# controller.net
KiCad netlist of a schematic drawn in EAGLE
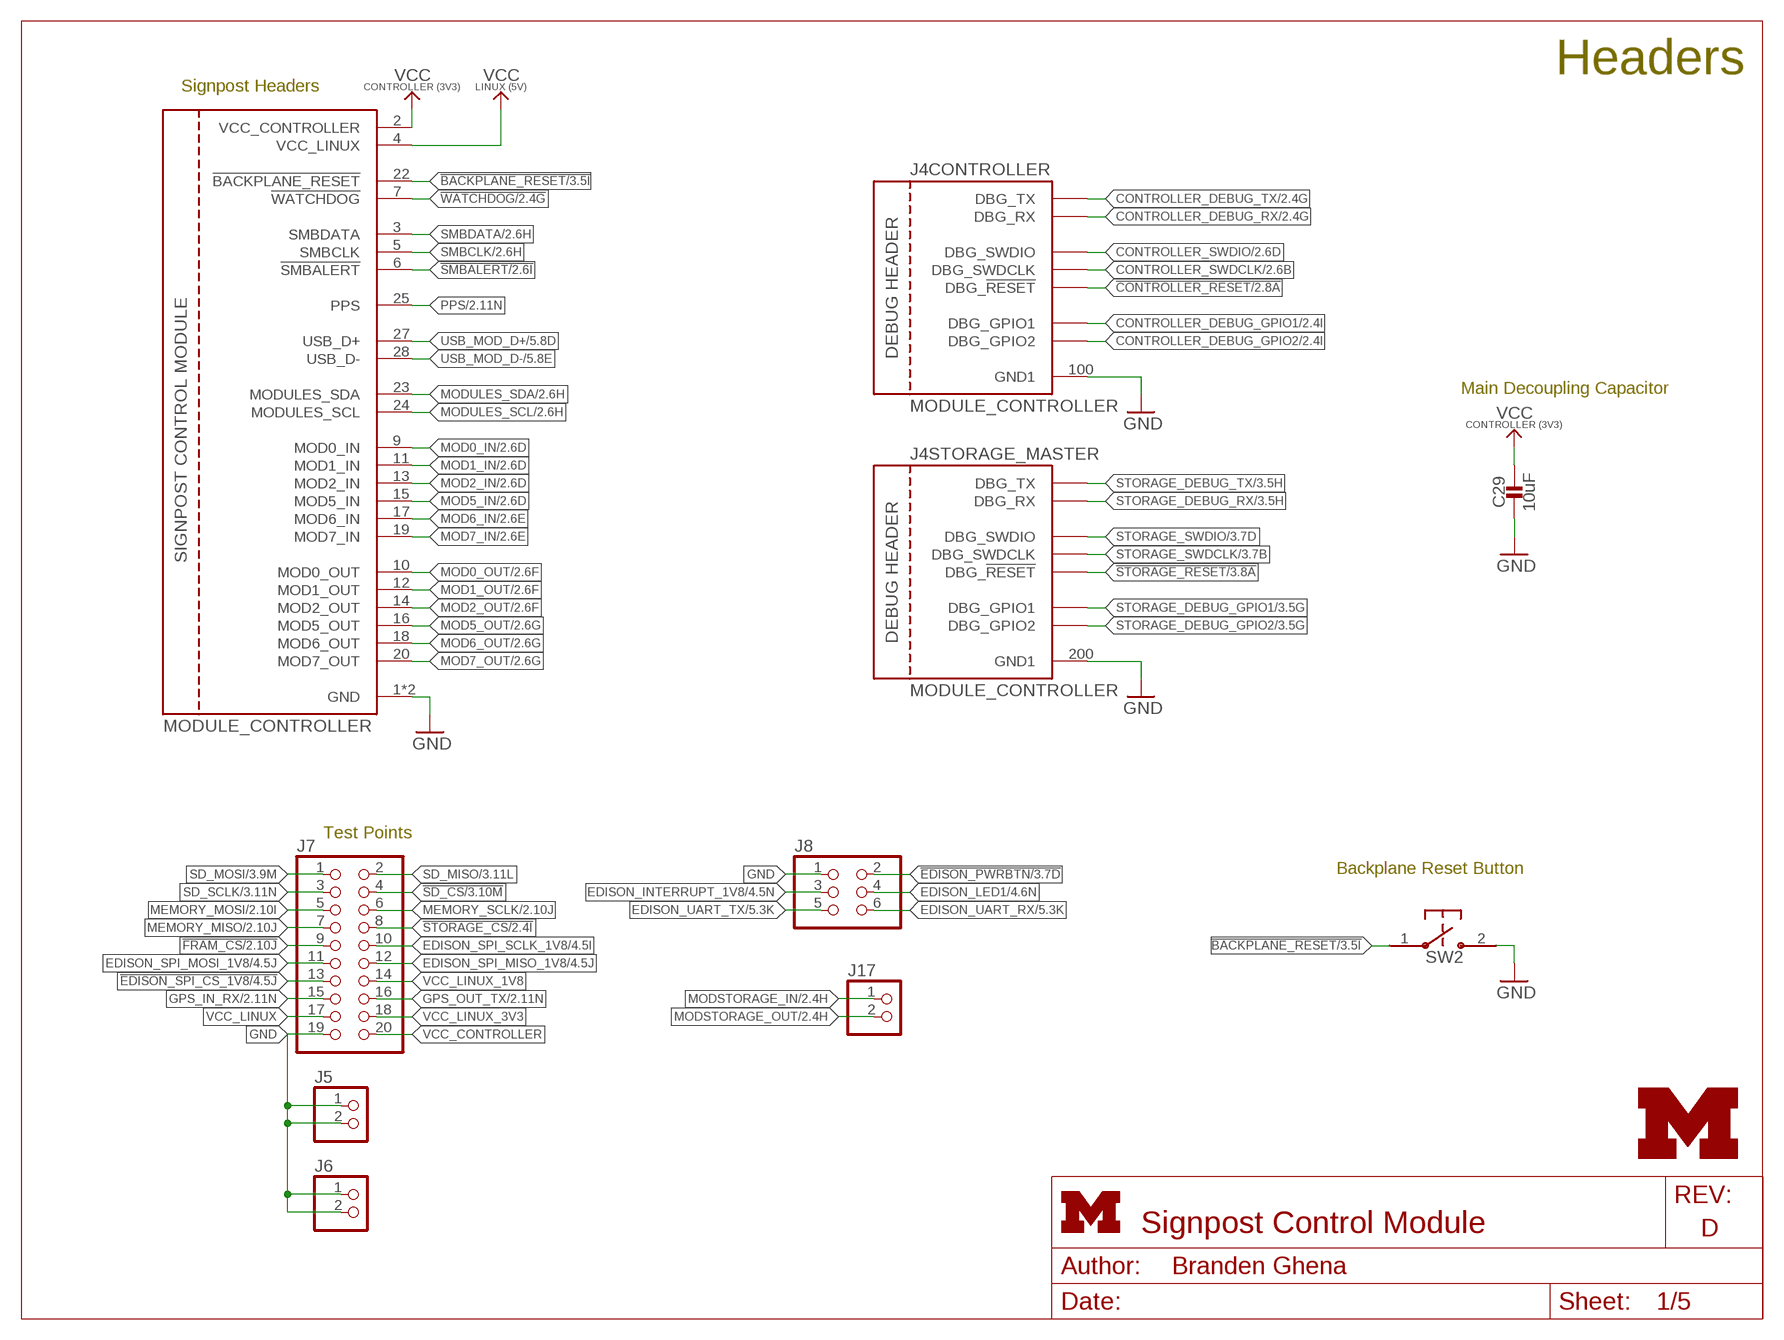
[diagram p0: schematic, sheet 1]
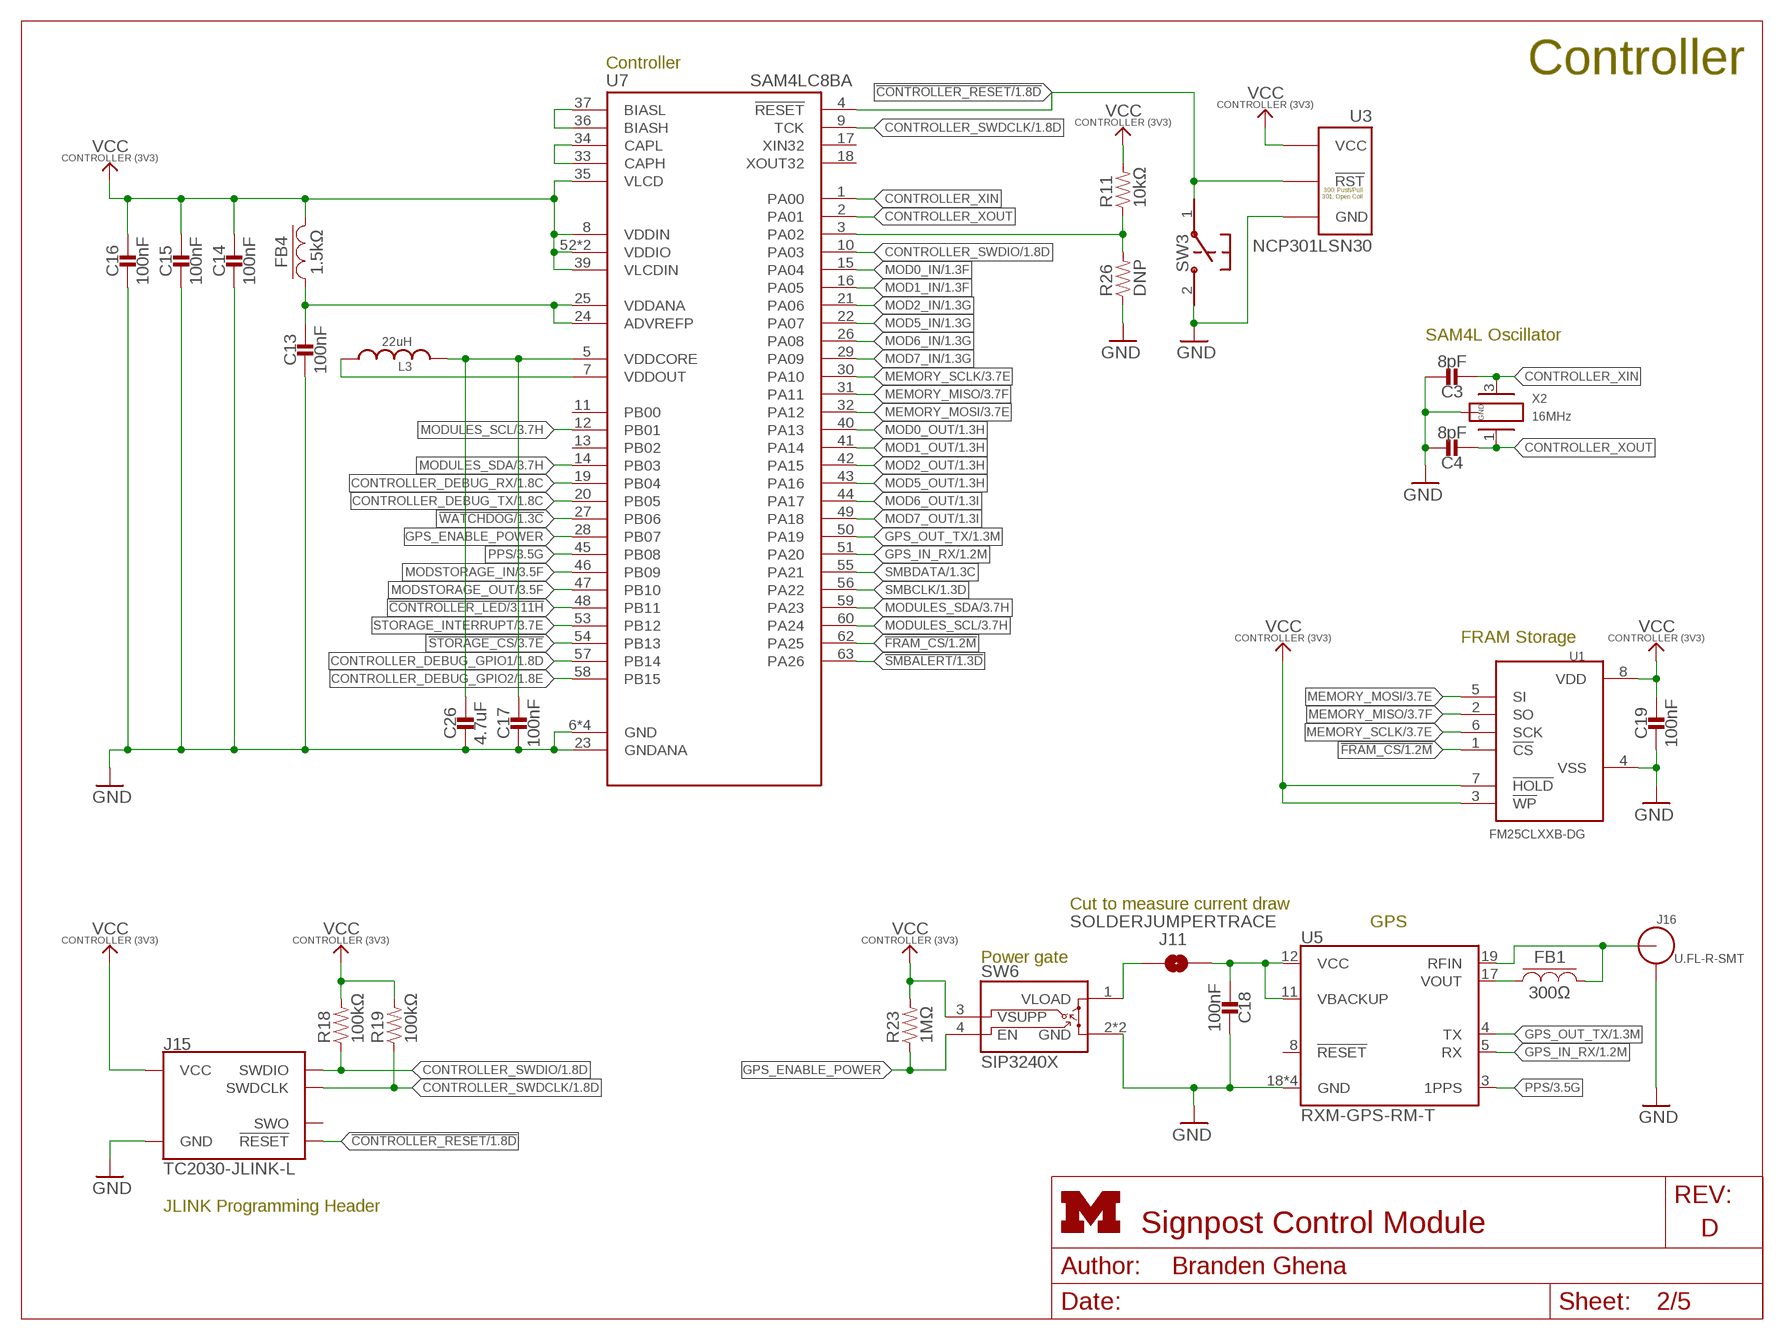
[diagram p1: schematic, sheet 2]
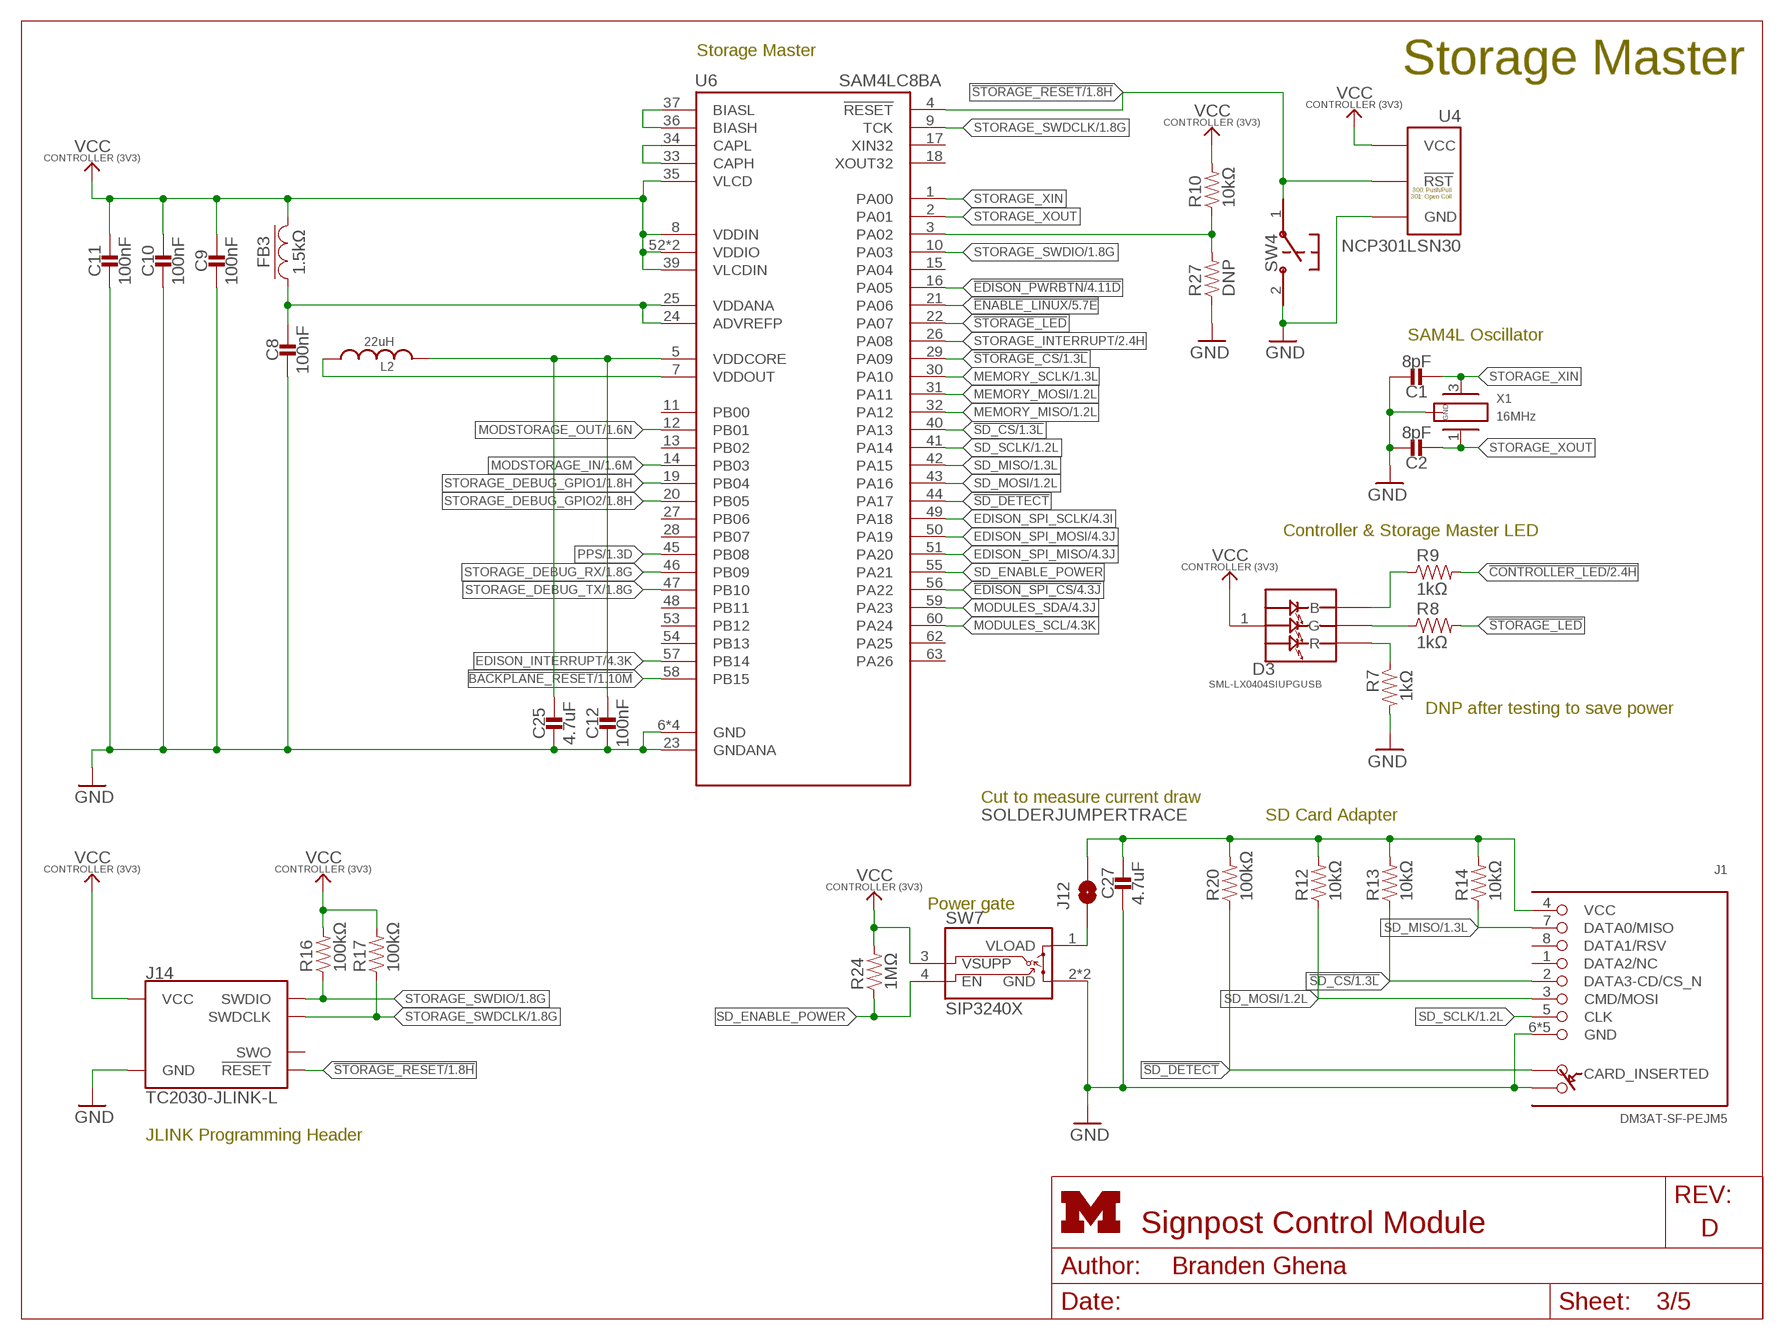
[diagram p2: schematic, sheet 3]
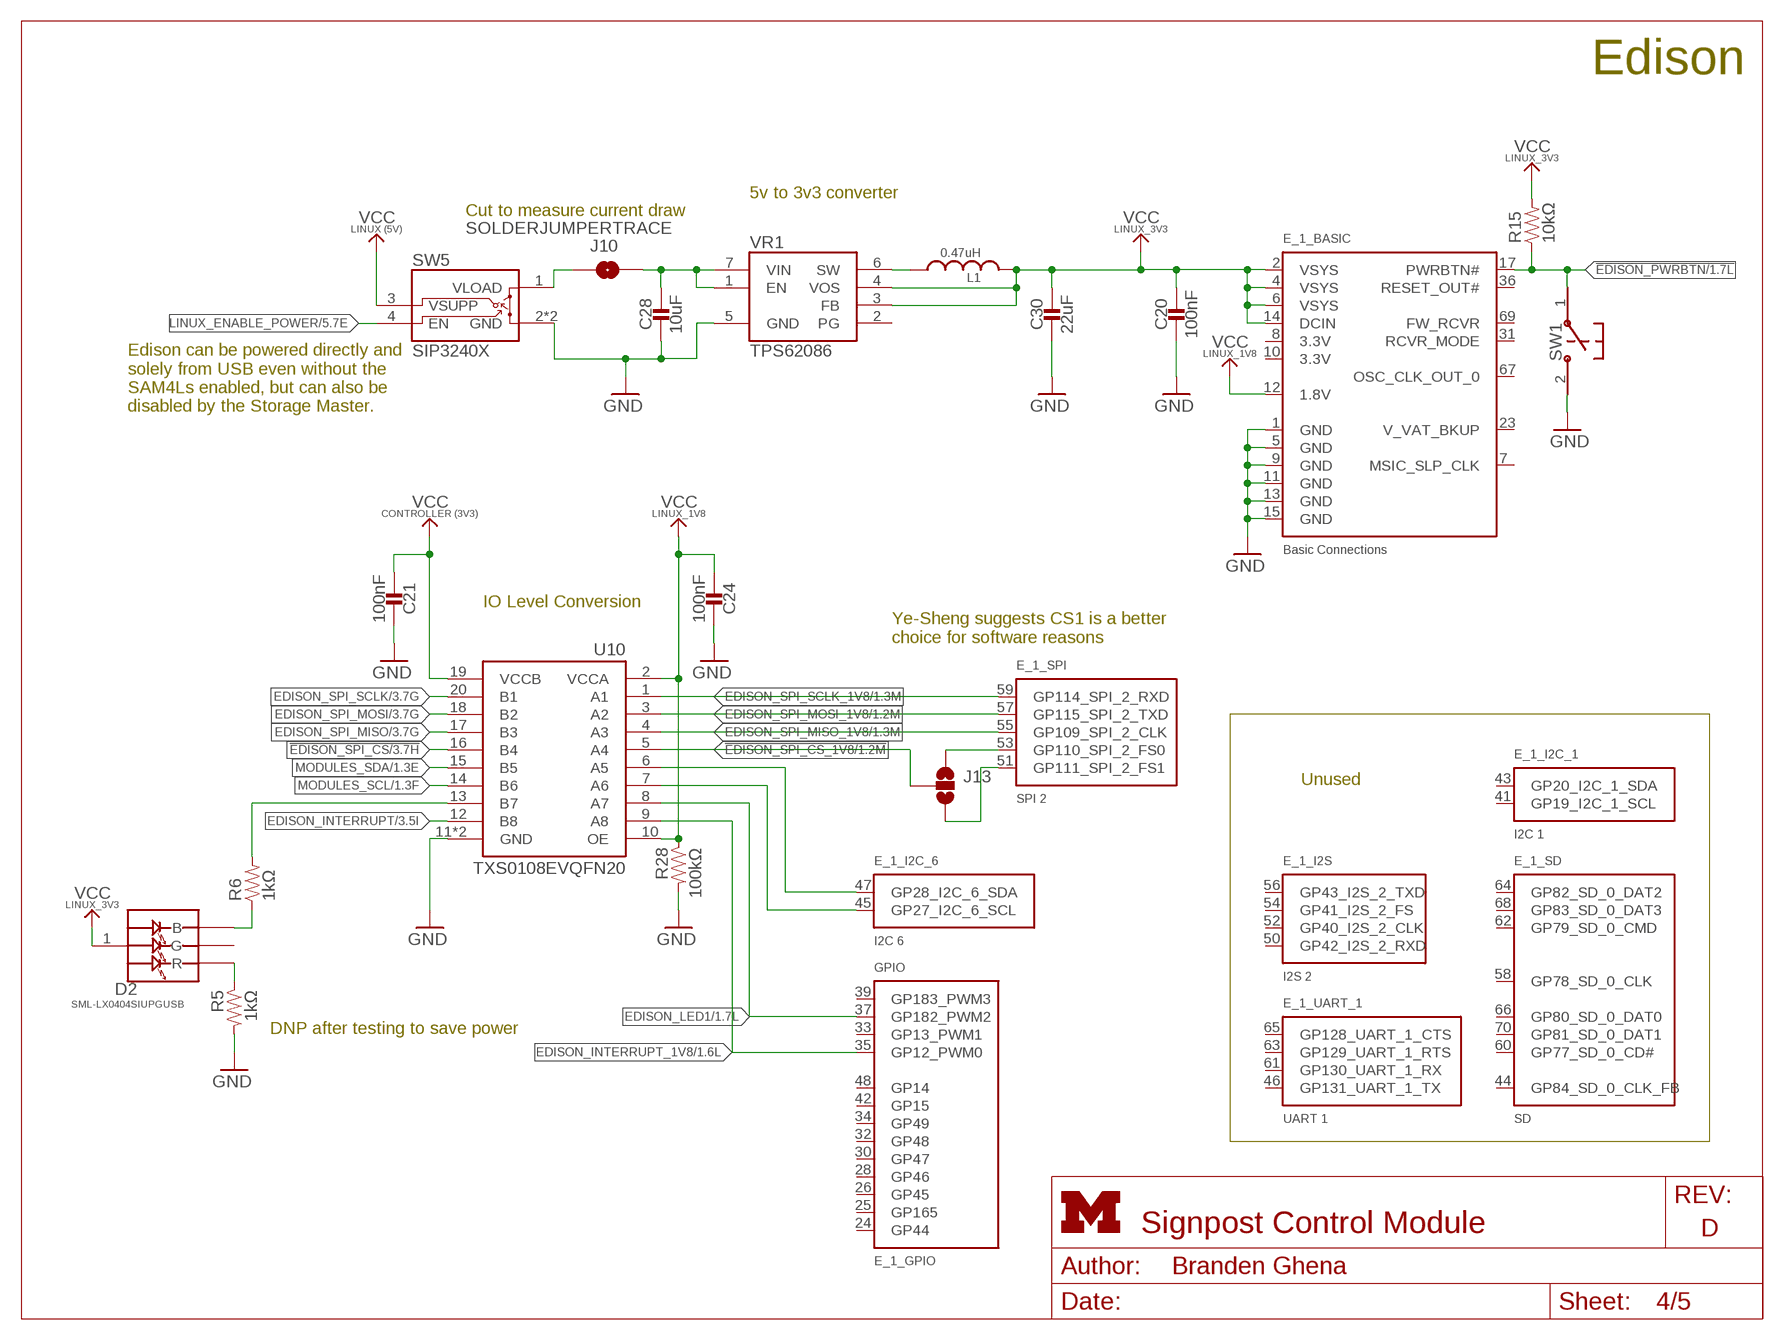
[diagram p3: schematic, sheet 4]
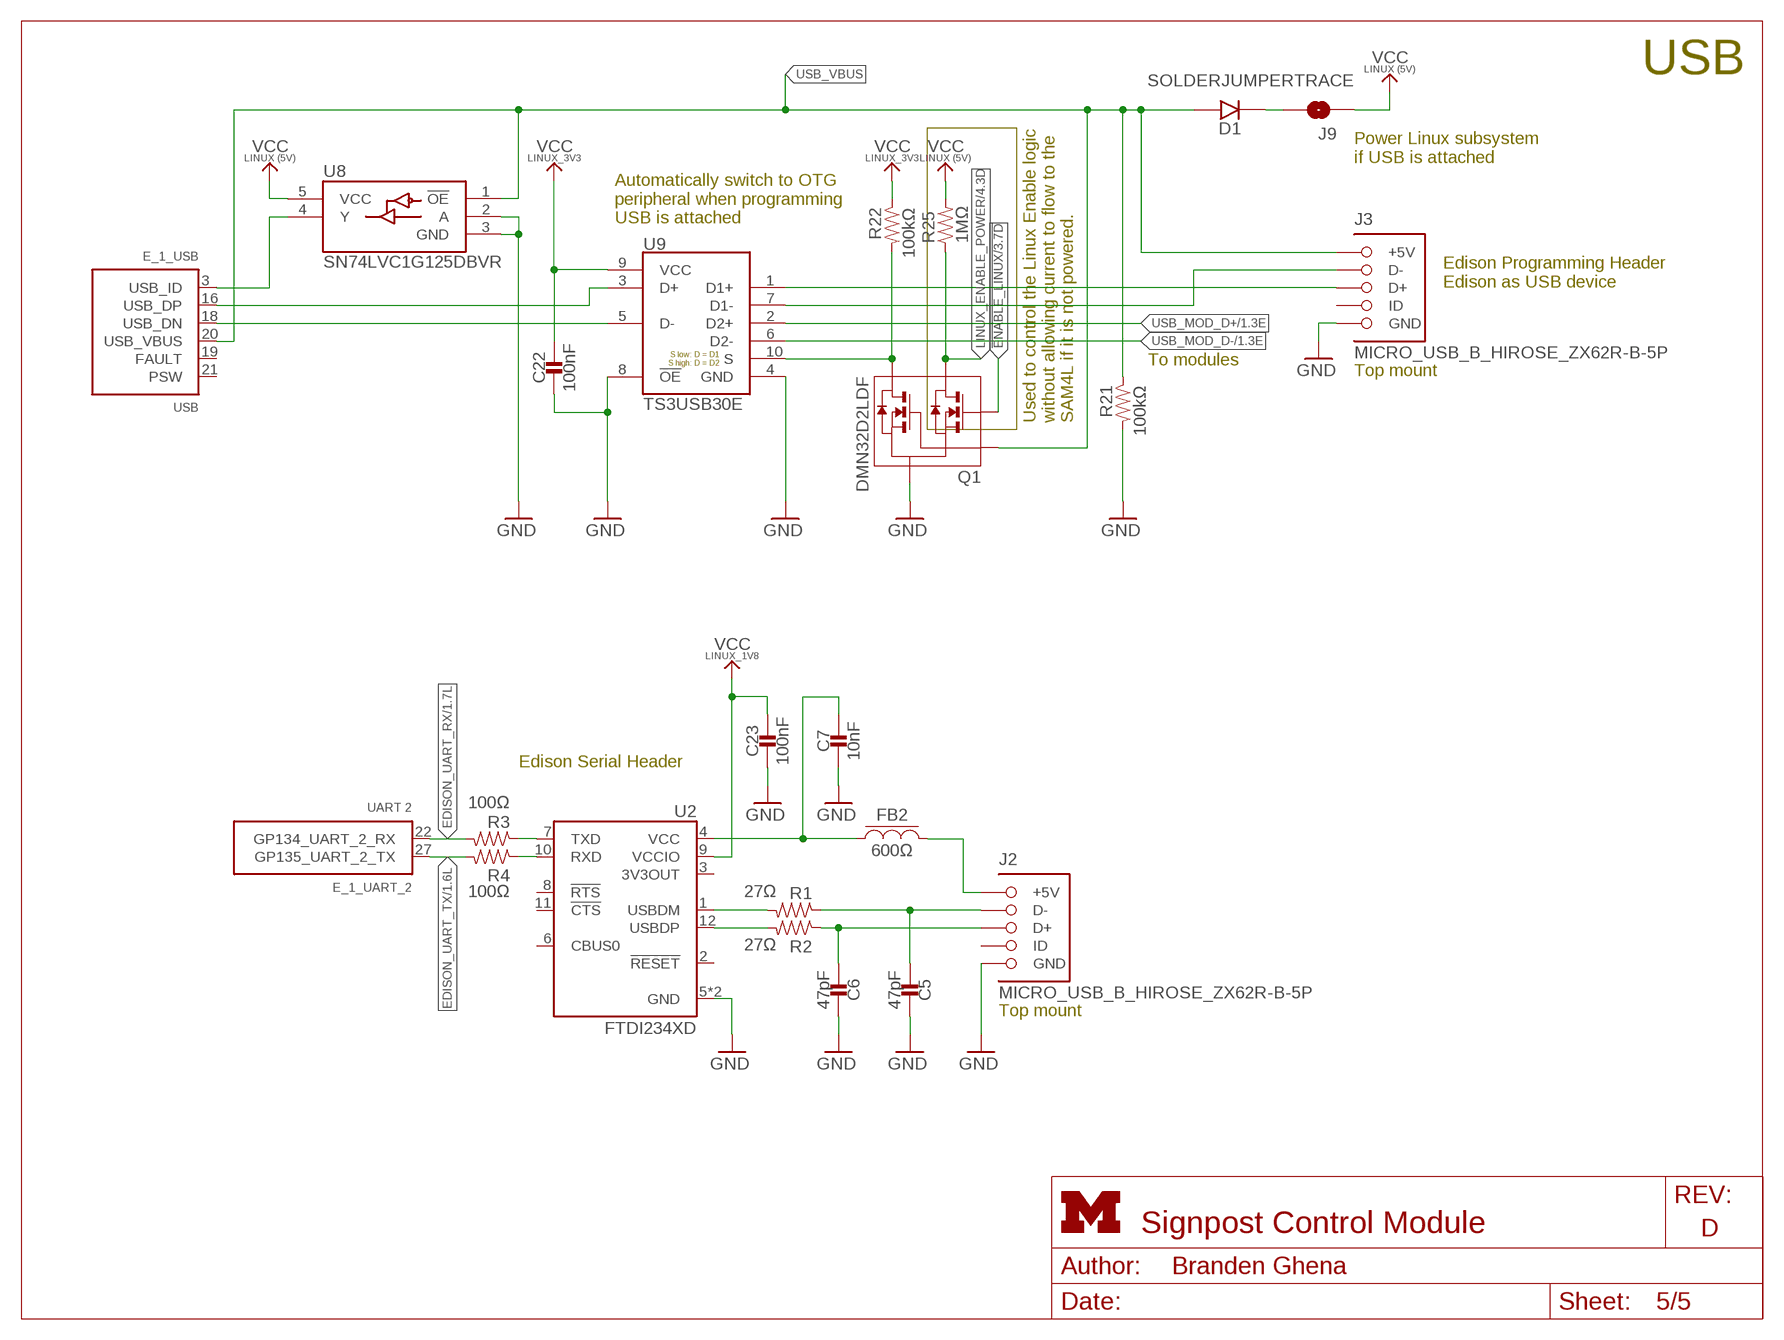
[diagram p4: schematic, sheet 5]

(export (version "E")
  (design (tool "Eeschema 10.0.6"))
  (components
    (comp (ref "C3")
      (value "8pF")
      (footprint "eagle-import:0402_CAP")
      (libsource (lib "eagle-import") (part "CAPACITOR0402_CAP"))
    )
    (comp (ref "C4")
      (value "8pF")
      (footprint "eagle-import:0402_CAP")
      (libsource (lib "eagle-import") (part "CAPACITOR0402_CAP"))
    )
    (comp (ref "C13")
      (value "100nF")
      (footprint "eagle-import:0402_CAP")
      (libsource (lib "eagle-import") (part "CAPACITOR0402_CAP"))
    )
    (comp (ref "C14")
      (value "100nF")
      (footprint "eagle-import:0402_CAP")
      (libsource (lib "eagle-import") (part "CAPACITOR0402_CAP"))
    )
    (comp (ref "C15")
      (value "100nF")
      (footprint "eagle-import:0402_CAP")
      (libsource (lib "eagle-import") (part "CAPACITOR0402_CAP"))
    )
    (comp (ref "C16")
      (value "100nF")
      (footprint "eagle-import:0402_CAP")
      (libsource (lib "eagle-import") (part "CAPACITOR0402_CAP"))
    )
    (comp (ref "C17")
      (value "100nF")
      (footprint "eagle-import:0402_CAP")
      (libsource (lib "eagle-import") (part "CAPACITOR0402_CAP"))
    )
    (comp (ref "C18")
      (value "100nF")
      (footprint "eagle-import:0402_CAP")
      (libsource (lib "eagle-import") (part "CAPACITOR0402_CAP"))
    )
    (comp (ref "C19")
      (value "100nF")
      (footprint "eagle-import:0402_CAP")
      (libsource (lib "eagle-import") (part "CAPACITOR0402_CAP"))
    )
    (comp (ref "C26")
      (value "4.7uF")
      (footprint "eagle-import:0402_CAP")
      (libsource (lib "eagle-import") (part "CAPACITOR0402_CAP"))
    )
    (comp (ref "FB1")
      (value "300Ω")
      (footprint "eagle-import:0402_CAP")
      (libsource (lib "eagle-import") (part "FERRITE_BEAD0402"))
    )
    (comp (ref "FB4")
      (value "1.5kΩ")
      (footprint "eagle-import:0402_CAP")
      (libsource (lib "eagle-import") (part "FERRITE_BEAD0402"))
    )
    (comp (ref "J11")
      (value "SOLDERJUMPERTRACE")
      (footprint "eagle-import:SJ_2S-TRACE")
      (libsource (lib "eagle-import") (part "SOLDERJUMPERTRACE"))
    )
    (comp (ref "J15")
      (value "TC2030-JLINK-L")
      (footprint "eagle-import:TC2030-IDC")
      (libsource (lib "eagle-import") (part "TC2030-JLINK-L"))
    )
    (comp (ref "J16")
      (value "U.FL-R-SMT")
      (footprint "eagle-import:U.FL_SMT")
      (libsource (lib "eagle-import") (part "U.FL-R-SMT"))
    )
    (comp (ref "L3")
      (value "22uH")
      (footprint "eagle-import:1212")
      (libsource (lib "eagle-import") (part "LHQ3NP"))
    )
    (comp (ref "R11")
      (value "10kΩ")
      (footprint "eagle-import:0402_RES")
      (libsource (lib "eagle-import") (part "RESISTOR0402_RES"))
    )
    (comp (ref "R18")
      (value "100kΩ")
      (footprint "eagle-import:0402_RES")
      (libsource (lib "eagle-import") (part "RESISTOR0402_RES"))
    )
    (comp (ref "R19")
      (value "100kΩ")
      (footprint "eagle-import:0402_RES")
      (libsource (lib "eagle-import") (part "RESISTOR0402_RES"))
    )
    (comp (ref "R23")
      (value "1MΩ")
      (footprint "eagle-import:0402_RES")
      (libsource (lib "eagle-import") (part "RESISTOR0402_RES"))
    )
    (comp (ref "R26")
      (value "DNP")
      (footprint "eagle-import:0402_RES")
      (libsource (lib "eagle-import") (part "RESISTOR0402_RES"))
    )
    (comp (ref "SW3")
      (value "B3U-1000P")
      (footprint "eagle-import:B3U-1000P")
      (libsource (lib "eagle-import") (part "B3U-1000P"))
    )
    (comp (ref "SW6")
      (value "SIP3240X")
      (footprint "eagle-import:TDFN4")
      (libsource (lib "eagle-import") (part "SIP3240X"))
    )
    (comp (ref "U1")
      (value "FM25CLXXB-DG")
      (footprint "eagle-import:TDFN-8")
      (libsource (lib "eagle-import") (part "FM25CLXXB-DG"))
    )
    (comp (ref "U3")
      (value "NCP301LSN30")
      (footprint "eagle-import:SOT23-5")
      (libsource (lib "eagle-import") (part "NCP301LSN30"))
    )
    (comp (ref "U5")
      (value "RXM-GPS-RM-T")
      (footprint "eagle-import:RXM-GPS-RM-T")
      (libsource (lib "eagle-import") (part "RXM-GPS-RM-T"))
    )
    (comp (ref "U7")
      (value "SAM4LC8BA")
      (footprint "eagle-import:QFN-64-9MM")
      (libsource (lib "eagle-import") (part "SAM4LC8BA"))
    )
    (comp (ref "X2")
      (value "16MHz")
      (footprint "eagle-import:FHXXX")
      (libsource (lib "eagle-import") (part "FH1600015"))
    )
    (comp (ref "C20")
      (value "100nF")
      (footprint "eagle-import:0402_CAP")
      (libsource (lib "eagle-import") (part "CAPACITOR0402_CAP"))
    )
    (comp (ref "C21")
      (value "100nF")
      (footprint "eagle-import:0402_CAP")
      (libsource (lib "eagle-import") (part "CAPACITOR0402_CAP"))
    )
    (comp (ref "C24")
      (value "100nF")
      (footprint "eagle-import:0402_CAP")
      (libsource (lib "eagle-import") (part "CAPACITOR0402_CAP"))
    )
    (comp (ref "C28")
      (value "10uF")
      (footprint "eagle-import:0805_CAP")
      (libsource (lib "eagle-import") (part "CAPACITOR0805_CAP"))
    )
    (comp (ref "C30")
      (value "22uF")
      (footprint "eagle-import:0805_CAP")
      (libsource (lib "eagle-import") (part "CAPACITOR0805_CAP"))
    )
    (comp (ref "D2")
      (value "SML-LX0404SIUPGUSB")
      (footprint "eagle-import:1MM_SQ_4PAD")
      (libsource (lib "eagle-import") (part "SML-LX0404SIUPGUSB"))
    )
    (comp (ref "E_1")
      (value "EDISON_CONNECTOR_SEGMENTED")
      (footprint "eagle-import:EDISON_DAUGHTER")
      (fields (field (name "MOUSER") "798-DF40HC3070DS4V51") (field (name "AMAZON") "B00PTVSS4A"))
      (libsource (lib "eagle-import") (part "EDISON_CONNECTOR_SEGMENTED"))
    )
    (comp (ref "J10")
      (value "SOLDERJUMPERTRACE")
      (footprint "eagle-import:SJ_2S-TRACE")
      (libsource (lib "eagle-import") (part "SOLDERJUMPERTRACE"))
    )
    (comp (ref "J13")
      (value "SOLDERJUMPER_2WAYPASTE2&3")
      (footprint "eagle-import:SJ_3_PASTE2&3")
      (libsource (lib "eagle-import") (part "SOLDERJUMPER_2WAYPASTE2&3"))
    )
    (comp (ref "L1")
      (value "0.47uH")
      (footprint "eagle-import:DFE322512C")
      (libsource (lib "eagle-import") (part "INDUCTORDFE322512C"))
    )
    (comp (ref "R5")
      (value "1kΩ")
      (footprint "eagle-import:0402_RES")
      (libsource (lib "eagle-import") (part "RESISTOR0402_RES"))
    )
    (comp (ref "R6")
      (value "1kΩ")
      (footprint "eagle-import:0402_RES")
      (libsource (lib "eagle-import") (part "RESISTOR0402_RES"))
    )
    (comp (ref "R15")
      (value "10kΩ")
      (footprint "eagle-import:0402_RES")
      (libsource (lib "eagle-import") (part "RESISTOR0402_RES"))
    )
    (comp (ref "R28")
      (value "100kΩ")
      (footprint "eagle-import:0402_RES")
      (libsource (lib "eagle-import") (part "RESISTOR0402_RES"))
    )
    (comp (ref "SW1")
      (value "B3U-1000P")
      (footprint "eagle-import:B3U-1000P")
      (libsource (lib "eagle-import") (part "B3U-1000P"))
    )
    (comp (ref "SW5")
      (value "SIP3240X")
      (footprint "eagle-import:TDFN4")
      (libsource (lib "eagle-import") (part "SIP3240X"))
    )
    (comp (ref "U10")
      (value "TXS0108EVQFN20")
      (footprint "eagle-import:R-PVQFN-N20")
      (libsource (lib "eagle-import") (part "TXS0108EVQFN20"))
    )
    (comp (ref "VR1")
      (value "TPS62086")
      (footprint "eagle-import:RLT0007A")
      (libsource (lib "eagle-import") (part "TPS62086"))
    )
    (comp (ref "C1")
      (value "8pF")
      (footprint "eagle-import:0402_CAP")
      (libsource (lib "eagle-import") (part "CAPACITOR0402_CAP"))
    )
    (comp (ref "C2")
      (value "8pF")
      (footprint "eagle-import:0402_CAP")
      (libsource (lib "eagle-import") (part "CAPACITOR0402_CAP"))
    )
    (comp (ref "C8")
      (value "100nF")
      (footprint "eagle-import:0402_CAP")
      (libsource (lib "eagle-import") (part "CAPACITOR0402_CAP"))
    )
    (comp (ref "C9")
      (value "100nF")
      (footprint "eagle-import:0402_CAP")
      (libsource (lib "eagle-import") (part "CAPACITOR0402_CAP"))
    )
    (comp (ref "C10")
      (value "100nF")
      (footprint "eagle-import:0402_CAP")
      (libsource (lib "eagle-import") (part "CAPACITOR0402_CAP"))
    )
    (comp (ref "C11")
      (value "100nF")
      (footprint "eagle-import:0402_CAP")
      (libsource (lib "eagle-import") (part "CAPACITOR0402_CAP"))
    )
    (comp (ref "C12")
      (value "100nF")
      (footprint "eagle-import:0402_CAP")
      (libsource (lib "eagle-import") (part "CAPACITOR0402_CAP"))
    )
    (comp (ref "C25")
      (value "4.7uF")
      (footprint "eagle-import:0402_CAP")
      (libsource (lib "eagle-import") (part "CAPACITOR0402_CAP"))
    )
    (comp (ref "C27")
      (value "4.7uF")
      (footprint "eagle-import:0402_CAP")
      (libsource (lib "eagle-import") (part "CAPACITOR0402_CAP"))
    )
    (comp (ref "D3")
      (value "SML-LX0404SIUPGUSB")
      (footprint "eagle-import:1MM_SQ_4PAD")
      (libsource (lib "eagle-import") (part "SML-LX0404SIUPGUSB"))
    )
    (comp (ref "FB3")
      (value "1.5kΩ")
      (footprint "eagle-import:0402_CAP")
      (libsource (lib "eagle-import") (part "FERRITE_BEAD0402"))
    )
    (comp (ref "J1")
      (value "DM3AT-SF-PEJM5")
      (footprint "eagle-import:DM3AT-SF-PEJM5")
      (libsource (lib "eagle-import") (part "DM3AT-SF-PEJM5"))
    )
    (comp (ref "J12")
      (value "SOLDERJUMPERTRACE")
      (footprint "eagle-import:SJ_2S-TRACE")
      (libsource (lib "eagle-import") (part "SOLDERJUMPERTRACE"))
    )
    (comp (ref "J14")
      (value "TC2030-JLINK-L")
      (footprint "eagle-import:TC2030-IDC")
      (libsource (lib "eagle-import") (part "TC2030-JLINK-L"))
    )
    (comp (ref "L2")
      (value "22uH")
      (footprint "eagle-import:1212")
      (libsource (lib "eagle-import") (part "LHQ3NP"))
    )
    (comp (ref "R7")
      (value "1kΩ")
      (footprint "eagle-import:0402_RES")
      (libsource (lib "eagle-import") (part "RESISTOR0402_RES"))
    )
    (comp (ref "R8")
      (value "1kΩ")
      (footprint "eagle-import:0402_RES")
      (libsource (lib "eagle-import") (part "RESISTOR0402_RES"))
    )
    (comp (ref "R9")
      (value "1kΩ")
      (footprint "eagle-import:0402_RES")
      (libsource (lib "eagle-import") (part "RESISTOR0402_RES"))
    )
    (comp (ref "R10")
      (value "10kΩ")
      (footprint "eagle-import:0402_RES")
      (libsource (lib "eagle-import") (part "RESISTOR0402_RES"))
    )
    (comp (ref "R12")
      (value "10kΩ")
      (footprint "eagle-import:0402_RES")
      (libsource (lib "eagle-import") (part "RESISTOR0402_RES"))
    )
    (comp (ref "R13")
      (value "10kΩ")
      (footprint "eagle-import:0402_RES")
      (libsource (lib "eagle-import") (part "RESISTOR0402_RES"))
    )
    (comp (ref "R14")
      (value "10kΩ")
      (footprint "eagle-import:0402_RES")
      (libsource (lib "eagle-import") (part "RESISTOR0402_RES"))
    )
    (comp (ref "R16")
      (value "100kΩ")
      (footprint "eagle-import:0402_RES")
      (libsource (lib "eagle-import") (part "RESISTOR0402_RES"))
    )
    (comp (ref "R17")
      (value "100kΩ")
      (footprint "eagle-import:0402_RES")
      (libsource (lib "eagle-import") (part "RESISTOR0402_RES"))
    )
    (comp (ref "R20")
      (value "100kΩ")
      (footprint "eagle-import:0402_RES")
      (libsource (lib "eagle-import") (part "RESISTOR0402_RES"))
    )
    (comp (ref "R24")
      (value "1MΩ")
      (footprint "eagle-import:0402_RES")
      (libsource (lib "eagle-import") (part "RESISTOR0402_RES"))
    )
    (comp (ref "R27")
      (value "DNP")
      (footprint "eagle-import:0402_RES")
      (libsource (lib "eagle-import") (part "RESISTOR0402_RES"))
    )
    (comp (ref "SW4")
      (value "B3U-1000P")
      (footprint "eagle-import:B3U-1000P")
      (libsource (lib "eagle-import") (part "B3U-1000P"))
    )
    (comp (ref "SW7")
      (value "SIP3240X")
      (footprint "eagle-import:TDFN4")
      (libsource (lib "eagle-import") (part "SIP3240X"))
    )
    (comp (ref "U4")
      (value "NCP301LSN30")
      (footprint "eagle-import:SOT23-5")
      (libsource (lib "eagle-import") (part "NCP301LSN30"))
    )
    (comp (ref "U6")
      (value "SAM4LC8BA")
      (footprint "eagle-import:QFN-64-9MM")
      (libsource (lib "eagle-import") (part "SAM4LC8BA"))
    )
    (comp (ref "X1")
      (value "16MHz")
      (footprint "eagle-import:FHXXX")
      (libsource (lib "eagle-import") (part "FH1600015"))
    )
    (comp (ref "C5")
      (value "47pF")
      (footprint "eagle-import:0402_CAP")
      (libsource (lib "eagle-import") (part "CAPACITOR0402_CAP"))
    )
    (comp (ref "C6")
      (value "47pF")
      (footprint "eagle-import:0402_CAP")
      (libsource (lib "eagle-import") (part "CAPACITOR0402_CAP"))
    )
    (comp (ref "C7")
      (value "10nF")
      (footprint "eagle-import:0402_CAP")
      (libsource (lib "eagle-import") (part "CAPACITOR0402_CAP"))
    )
    (comp (ref "C22")
      (value "100nF")
      (footprint "eagle-import:0402_CAP")
      (libsource (lib "eagle-import") (part "CAPACITOR0402_CAP"))
    )
    (comp (ref "C23")
      (value "100nF")
      (footprint "eagle-import:0402_CAP")
      (libsource (lib "eagle-import") (part "CAPACITOR0402_CAP"))
    )
    (comp (ref "D1")
      (value "DIODE")
      (footprint "eagle-import:0805_DIODE")
      (libsource (lib "eagle-import") (part "DIODE"))
    )
    (comp (ref "FB2")
      (value "600Ω")
      (footprint "eagle-import:0805_CAP")
      (libsource (lib "eagle-import") (part "FERRITE_BEAD0805"))
    )
    (comp (ref "J2")
      (value "MICRO_USB_B_HIROSE_ZX62R-B-5P")
      (footprint "eagle-import:USB_MICRO_B-HIROSE-ZX62R-B-5P")
      (fields (field (name "DIGIKEY") "H125274CT-ND"))
      (libsource (lib "eagle-import") (part "MICRO_USB_B_HIROSE_ZX62R-B-5P"))
    )
    (comp (ref "J3")
      (value "MICRO_USB_B_HIROSE_ZX62R-B-5P")
      (footprint "eagle-import:USB_MICRO_B-HIROSE-ZX62R-B-5P")
      (fields (field (name "DIGIKEY") "H125274CT-ND"))
      (libsource (lib "eagle-import") (part "MICRO_USB_B_HIROSE_ZX62R-B-5P"))
    )
    (comp (ref "J9")
      (value "SOLDERJUMPERTRACE")
      (footprint "eagle-import:SJ_2S-TRACE")
      (libsource (lib "eagle-import") (part "SOLDERJUMPERTRACE"))
    )
    (comp (ref "Q1")
      (value "DMN32D2LDF")
      (footprint "eagle-import:SOT353")
      (libsource (lib "eagle-import") (part "DMN32D2LDF"))
    )
    (comp (ref "R1")
      (value "27Ω")
      (footprint "eagle-import:0402_RES")
      (libsource (lib "eagle-import") (part "RESISTOR0402_RES"))
    )
    (comp (ref "R2")
      (value "27Ω")
      (footprint "eagle-import:0402_RES")
      (libsource (lib "eagle-import") (part "RESISTOR0402_RES"))
    )
    (comp (ref "R3")
      (value "100Ω")
      (footprint "eagle-import:0402_RES")
      (libsource (lib "eagle-import") (part "RESISTOR0402_RES"))
    )
    (comp (ref "R4")
      (value "100Ω")
      (footprint "eagle-import:0402_RES")
      (libsource (lib "eagle-import") (part "RESISTOR0402_RES"))
    )
    (comp (ref "R21")
      (value "100kΩ")
      (footprint "eagle-import:0402_RES")
      (libsource (lib "eagle-import") (part "RESISTOR0402_RES"))
    )
    (comp (ref "R22")
      (value "100kΩ")
      (footprint "eagle-import:0402_RES")
      (libsource (lib "eagle-import") (part "RESISTOR0402_RES"))
    )
    (comp (ref "R25")
      (value "1MΩ")
      (footprint "eagle-import:0402_RES")
      (libsource (lib "eagle-import") (part "RESISTOR0402_RES"))
    )
    (comp (ref "U2")
      (value "FTDI234XD")
      (footprint "eagle-import:DFN-12_3MM")
      (libsource (lib "eagle-import") (part "FTDI234XD"))
    )
    (comp (ref "U8")
      (value "SN74LVC1G125DBVR")
      (footprint "eagle-import:SOT-23-5")
      (libsource (lib "eagle-import") (part "SN74LVC1G125DBVR"))
    )
    (comp (ref "U9")
      (value "TS3USB30E")
      (footprint "eagle-import:UQFN-10")
      (libsource (lib "eagle-import") (part "TS3USB30E"))
    )
    (comp (ref "C29")
      (value "10uF")
      (footprint "eagle-import:0402_CAP")
      (libsource (lib "eagle-import") (part "CAPACITOR0402_CAP"))
    )
    (comp (ref "J4")
      (value "MODULE_CONTROLLER")
      (footprint "eagle-import:MODULE_CONTROLLER")
      (libsource (lib "eagle-import") (part "MODULE_CONTROLLER"))
    )
    (comp (ref "J5")
      (value "PINHD-1X2")
      (footprint "eagle-import:1X02")
      (libsource (lib "eagle-import") (part "PINHD-1X2"))
    )
    (comp (ref "J6")
      (value "PINHD-1X2")
      (footprint "eagle-import:1X02")
      (libsource (lib "eagle-import") (part "PINHD-1X2"))
    )
    (comp (ref "J7")
      (value "PINHD-2X10")
      (footprint "eagle-import:2X10")
      (libsource (lib "eagle-import") (part "PINHD-2X10"))
    )
    (comp (ref "J8")
      (value "PINHD-2X3")
      (footprint "eagle-import:2X03")
      (libsource (lib "eagle-import") (part "PINHD-2X3"))
    )
    (comp (ref "J17")
      (value "PINHD-1X2")
      (footprint "eagle-import:1X02")
      (libsource (lib "eagle-import") (part "pinhead_325_PINHD-1X2"))
    )
    (comp (ref "LOGO1")
      (value "UMICH_SOLID_MEDIUM")
      (footprint "eagle-import:UMICH_SOLID_200MIL")
      (libsource (lib "eagle-import") (part "UMICH_SOLID_MEDIUM"))
    )
    (comp (ref "SW2")
      (value "B3U-1000P")
      (footprint "eagle-import:B3U-1000P")
      (libsource (lib "eagle-import") (part "B3U-1000P"))
    )
  )
  (nets
    (net (code "1") (name "CONTROLLER_DEBUG_GPIO1") (class "Default")
      (node (ref "J4") (pin "101") (pinfunction "DBG_GPIO1_101") (pintype "bidirectional"))
      (node (ref "U7") (pin "57") (pinfunction "PB14_57") (pintype "bidirectional"))
    )
    (net (code "2") (name "CONTROLLER_DEBUG_GPIO2") (class "Default")
      (node (ref "J4") (pin "104") (pinfunction "DBG_GPIO2_104") (pintype "bidirectional"))
      (node (ref "U7") (pin "58") (pinfunction "PB15_58") (pintype "bidirectional"))
    )
    (net (code "3") (name "CONTROLLER_DEBUG_RX") (class "Default")
      (node (ref "J4") (pin "103") (pinfunction "DBG_RX_103") (pintype "bidirectional"))
      (node (ref "U7") (pin "19") (pinfunction "PB04_19") (pintype "bidirectional"))
    )
    (net (code "4") (name "CONTROLLER_DEBUG_TX") (class "Default")
      (node (ref "J4") (pin "102") (pinfunction "DBG_TX_102") (pintype "bidirectional"))
      (node (ref "U7") (pin "20") (pinfunction "PB05_20") (pintype "bidirectional"))
    )
    (net (code "5") (name "CONTROLLER_SWDCLK") (class "Default")
      (node (ref "J15") (pin "4") (pinfunction "SWDCLK_4") (pintype "bidirectional"))
      (node (ref "J4") (pin "106") (pinfunction "DBG_SWDCLK_106") (pintype "bidirectional"))
      (node (ref "R19") (pin "1") (pinfunction "1_1") (pintype "passive"))
      (node (ref "U7") (pin "9") (pinfunction "TCK_9") (pintype "bidirectional"))
    )
    (net (code "6") (name "CONTROLLER_SWDIO") (class "Default")
      (node (ref "J15") (pin "2") (pinfunction "SWDIO_2") (pintype "bidirectional"))
      (node (ref "J4") (pin "107") (pinfunction "DBG_SWDIO_107") (pintype "bidirectional"))
      (node (ref "R18") (pin "1") (pinfunction "1_1") (pintype "passive"))
      (node (ref "U7") (pin "10") (pinfunction "PA03_10") (pintype "bidirectional"))
    )
    (net (code "7") (name "CONTROLLER_XIN") (class "Default")
      (node (ref "C3") (pin "1") (pinfunction "1_1") (pintype "bidirectional"))
      (node (ref "U7") (pin "1") (pinfunction "PA00_1") (pintype "bidirectional"))
      (node (ref "X2") (pin "3") (pinfunction "2_3") (pintype "bidirectional"))
    )
    (net (code "8") (name "CONTROLLER_XOUT") (class "Default")
      (node (ref "C4") (pin "1") (pinfunction "1_1") (pintype "bidirectional"))
      (node (ref "U7") (pin "2") (pinfunction "PA01_2") (pintype "bidirectional"))
      (node (ref "X2") (pin "1") (pinfunction "1_1") (pintype "bidirectional"))
    )
    (net (code "9") (name "EDISON_INTERRUPT") (class "Default")
      (node (ref "U10") (pin "12") (pinfunction "B8_12") (pintype "bidirectional"))
      (node (ref "U6") (pin "57") (pinfunction "PB14_57") (pintype "bidirectional"))
    )
    (net (code "10") (name "EDISON_INTERRUPT_1V8") (class "Default")
      (node (ref "E_1") (pin "35") (pinfunction "GP12_PWM0_35") (pintype "bidirectional"))
      (node (ref "J8") (pin "3") (pinfunction "3_3") (pintype "passive"))
      (node (ref "U10") (pin "9") (pinfunction "A8_9") (pintype "bidirectional"))
    )
    (net (code "11") (name "EDISON_LED1") (class "Default")
      (node (ref "E_1") (pin "37") (pinfunction "GP182_PWM2_37") (pintype "bidirectional"))
      (node (ref "J8") (pin "4") (pinfunction "4_4") (pintype "passive"))
      (node (ref "U10") (pin "8") (pinfunction "A7_8") (pintype "bidirectional"))
    )
    (net (code "12") (name "EDISON_SPI_MISO") (class "Default")
      (node (ref "U10") (pin "17") (pinfunction "B3_17") (pintype "bidirectional"))
      (node (ref "U6") (pin "51") (pinfunction "PA20_51") (pintype "bidirectional"))
    )
    (net (code "13") (name "EDISON_SPI_MISO_1V8") (class "Default")
      (node (ref "E_1") (pin "55") (pinfunction "GP109_SPI_2_CLK_55") (pintype "bidirectional"))
      (node (ref "J7") (pin "12") (pinfunction "12_12") (pintype "passive"))
      (node (ref "U10") (pin "4") (pinfunction "A3_4") (pintype "bidirectional"))
    )
    (net (code "14") (name "EDISON_SPI_MOSI") (class "Default")
      (node (ref "U10") (pin "18") (pinfunction "B2_18") (pintype "bidirectional"))
      (node (ref "U6") (pin "50") (pinfunction "PA19_50") (pintype "bidirectional"))
    )
    (net (code "15") (name "EDISON_SPI_MOSI_1V8") (class "Default")
      (node (ref "E_1") (pin "57") (pinfunction "GP115_SPI_2_TXD_57") (pintype "bidirectional"))
      (node (ref "J7") (pin "11") (pinfunction "11_11") (pintype "passive"))
      (node (ref "U10") (pin "3") (pinfunction "A2_3") (pintype "bidirectional"))
    )
    (net (code "16") (name "EDISON_SPI_SCLK") (class "Default")
      (node (ref "U10") (pin "20") (pinfunction "B1_20") (pintype "bidirectional"))
      (node (ref "U6") (pin "49") (pinfunction "PA18_49") (pintype "bidirectional"))
    )
    (net (code "17") (name "EDISON_SPI_SCLK_1V8") (class "Default")
      (node (ref "E_1") (pin "59") (pinfunction "GP114_SPI_2_RXD_59") (pintype "bidirectional"))
      (node (ref "J7") (pin "10") (pinfunction "10_10") (pintype "passive"))
      (node (ref "U10") (pin "1") (pinfunction "A1_1") (pintype "bidirectional"))
    )
    (net (code "18") (name "EDISON_UART_RX") (class "Default")
      (node (ref "E_1") (pin "22") (pinfunction "GP134_UART_2_RX_22") (pintype "bidirectional"))
      (node (ref "J8") (pin "6") (pinfunction "6_6") (pintype "passive"))
      (node (ref "R3") (pin "2") (pinfunction "2_2") (pintype "passive"))
    )
    (net (code "19") (name "EDISON_UART_TX") (class "Default")
      (node (ref "E_1") (pin "27") (pinfunction "GP135_UART_2_TX_27") (pintype "bidirectional"))
      (node (ref "J8") (pin "5") (pinfunction "5_5") (pintype "passive"))
      (node (ref "R4") (pin "2") (pinfunction "2_2") (pintype "passive"))
    )
    (net (code "20") (name "GND") (class "Default")
      (node (ref "C1") (pin "2") (pinfunction "2_2") (pintype "bidirectional"))
      (node (ref "C10") (pin "2") (pinfunction "2_2") (pintype "bidirectional"))
      (node (ref "C11") (pin "2") (pinfunction "2_2") (pintype "bidirectional"))
      (node (ref "C12") (pin "2") (pinfunction "2_2") (pintype "bidirectional"))
      (node (ref "C13") (pin "2") (pinfunction "2_2") (pintype "bidirectional"))
      (node (ref "C14") (pin "2") (pinfunction "2_2") (pintype "bidirectional"))
      (node (ref "C15") (pin "2") (pinfunction "2_2") (pintype "bidirectional"))
      (node (ref "C16") (pin "2") (pinfunction "2_2") (pintype "bidirectional"))
      (node (ref "C17") (pin "2") (pinfunction "2_2") (pintype "bidirectional"))
      (node (ref "C18") (pin "2") (pinfunction "2_2") (pintype "bidirectional"))
      (node (ref "C19") (pin "2") (pinfunction "2_2") (pintype "bidirectional"))
      (node (ref "C2") (pin "2") (pinfunction "2_2") (pintype "bidirectional"))
      (node (ref "C20") (pin "2") (pinfunction "2_2") (pintype "bidirectional"))
      (node (ref "C21") (pin "1") (pinfunction "1_1") (pintype "bidirectional"))
      (node (ref "C22") (pin "2") (pinfunction "2_2") (pintype "bidirectional"))
      (node (ref "C23") (pin "2") (pinfunction "2_2") (pintype "bidirectional"))
      (node (ref "C24") (pin "1") (pinfunction "1_1") (pintype "bidirectional"))
      (node (ref "C25") (pin "2") (pinfunction "2_2") (pintype "bidirectional"))
      (node (ref "C26") (pin "2") (pinfunction "2_2") (pintype "bidirectional"))
      (node (ref "C27") (pin "2") (pinfunction "2_2") (pintype "bidirectional"))
      (node (ref "C28") (pin "P$2") (pinfunction "2_P$2") (pintype "bidirectional"))
      (node (ref "C29") (pin "2") (pinfunction "2_2") (pintype "bidirectional"))
      (node (ref "C3") (pin "2") (pinfunction "2_2") (pintype "bidirectional"))
      (node (ref "C30") (pin "P$2") (pinfunction "2_P$2") (pintype "bidirectional"))
      (node (ref "C4") (pin "2") (pinfunction "2_2") (pintype "bidirectional"))
      (node (ref "C5") (pin "2") (pinfunction "2_2") (pintype "bidirectional"))
      (node (ref "C6") (pin "2") (pinfunction "2_2") (pintype "bidirectional"))
      (node (ref "C7") (pin "2") (pinfunction "2_2") (pintype "bidirectional"))
      (node (ref "C8") (pin "2") (pinfunction "2_2") (pintype "bidirectional"))
      (node (ref "C9") (pin "2") (pinfunction "2_2") (pintype "bidirectional"))
      (node (ref "E_1") (pin "1") (pinfunction "GND_1") (pintype "bidirectional"))
      (node (ref "E_1") (pin "11") (pinfunction "GND_11") (pintype "bidirectional"))
      (node (ref "E_1") (pin "13") (pinfunction "GND_13") (pintype "bidirectional"))
      (node (ref "E_1") (pin "15") (pinfunction "GND_15") (pintype "bidirectional"))
      (node (ref "E_1") (pin "5") (pinfunction "GND_5") (pintype "bidirectional"))
      (node (ref "E_1") (pin "9") (pinfunction "GND_9") (pintype "bidirectional"))
      (node (ref "J1") (pin "6") (pinfunction "GND_6") (pintype "bidirectional"))
      (node (ref "J1") (pin "B") (pinfunction "B_B") (pintype "bidirectional"))
      (node (ref "J1") (pin "MOUNT0") (pinfunction "GND_MOUNT0") (pintype "bidirectional"))
      (node (ref "J1") (pin "MOUNT1") (pinfunction "GND_MOUNT1") (pintype "bidirectional"))
      (node (ref "J1") (pin "MOUNT2") (pinfunction "GND_MOUNT2") (pintype "bidirectional"))
      (node (ref "J1") (pin "MOUNT3") (pinfunction "GND_MOUNT3") (pintype "bidirectional"))
      (node (ref "J14") (pin "5") (pinfunction "GND_5") (pintype "bidirectional"))
      (node (ref "J15") (pin "5") (pinfunction "GND_5") (pintype "bidirectional"))
      (node (ref "J16") (pin "GND1") (pinfunction "P$2_GND1") (pintype "bidirectional"))
      (node (ref "J16") (pin "GND2") (pinfunction "P$2_GND2") (pintype "bidirectional"))
      (node (ref "J2") (pin "5") (pinfunction "GND_5") (pintype "bidirectional"))
      (node (ref "J3") (pin "5") (pinfunction "GND_5") (pintype "bidirectional"))
      (node (ref "J4") (pin "1") (pinfunction "GND_1") (pintype "bidirectional"))
      (node (ref "J4") (pin "100") (pinfunction "GND1_100") (pintype "bidirectional"))
      (node (ref "J4") (pin "200") (pinfunction "GND1_200") (pintype "bidirectional"))
      (node (ref "J4") (pin "21") (pinfunction "GND_21") (pintype "bidirectional"))
      (node (ref "J5") (pin "1") (pinfunction "1_1") (pintype "passive"))
      (node (ref "J5") (pin "2") (pinfunction "2_2") (pintype "passive"))
      (node (ref "J6") (pin "1") (pinfunction "1_1") (pintype "passive"))
      (node (ref "J6") (pin "2") (pinfunction "2_2") (pintype "passive"))
      (node (ref "J7") (pin "19") (pinfunction "19_19") (pintype "passive"))
      (node (ref "J8") (pin "1") (pinfunction "1_1") (pintype "passive"))
      (node (ref "Q1") (pin "S") (pinfunction "S_S") (pintype "bidirectional"))
      (node (ref "R21") (pin "2") (pinfunction "2_2") (pintype "passive"))
      (node (ref "R26") (pin "1") (pinfunction "1_1") (pintype "passive"))
      (node (ref "R27") (pin "1") (pinfunction "1_1") (pintype "passive"))
      (node (ref "R28") (pin "2") (pinfunction "2_2") (pintype "passive"))
      (node (ref "R5") (pin "2") (pinfunction "2_2") (pintype "passive"))
      (node (ref "R7") (pin "2") (pinfunction "2_2") (pintype "passive"))
      (node (ref "SW1") (pin "2") (pinfunction "P$2_2") (pintype "passive"))
      (node (ref "SW2") (pin "2") (pinfunction "P$2_2") (pintype "passive"))
      (node (ref "SW3") (pin "2") (pinfunction "P$2_2") (pintype "passive"))
      (node (ref "SW4") (pin "2") (pinfunction "P$2_2") (pintype "passive"))
      (node (ref "SW5") (pin "2") (pinfunction "GND_2") (pintype "bidirectional"))
      (node (ref "SW5") (pin "PAD") (pinfunction "GND_PAD") (pintype "bidirectional"))
      (node (ref "SW6") (pin "2") (pinfunction "GND_2") (pintype "bidirectional"))
      (node (ref "SW6") (pin "PAD") (pinfunction "GND_PAD") (pintype "bidirectional"))
      (node (ref "SW7") (pin "2") (pinfunction "GND_2") (pintype "bidirectional"))
      (node (ref "SW7") (pin "PAD") (pinfunction "GND_PAD") (pintype "bidirectional"))
      (node (ref "U1") (pin "4") (pinfunction "VSS_4") (pintype "bidirectional"))
      (node (ref "U10") (pin "11") (pinfunction "GND_11") (pintype "bidirectional"))
      (node (ref "U10") (pin "THERMAL") (pinfunction "GND_THERMAL") (pintype "bidirectional"))
      (node (ref "U2") (pin "13") (pinfunction "GND_13") (pintype "bidirectional"))
      (node (ref "U2") (pin "5") (pinfunction "GND_5") (pintype "bidirectional"))
      (node (ref "U3") (pin "3") (pinfunction "GND_3") (pintype "bidirectional"))
      (node (ref "U4") (pin "3") (pinfunction "GND_3") (pintype "bidirectional"))
      (node (ref "U5") (pin "18") (pinfunction "GND_18") (pintype "bidirectional"))
      (node (ref "U5") (pin "20") (pinfunction "GND_20") (pintype "bidirectional"))
      (node (ref "U5") (pin "21") (pinfunction "GND_21") (pintype "bidirectional"))
      (node (ref "U5") (pin "22") (pinfunction "GND_22") (pintype "bidirectional"))
      (node (ref "U6") (pin "23") (pinfunction "GNDANA_23") (pintype "power_in"))
      (node (ref "U6") (pin "38") (pinfunction "GND_38") (pintype "power_in"))
      (node (ref "U6") (pin "6") (pinfunction "GND_6") (pintype "power_in"))
      (node (ref "U6") (pin "64") (pinfunction "GND_64") (pintype "power_in"))
      (node (ref "U6") (pin "GND") (pinfunction "GND_GND") (pintype "power_in"))
      (node (ref "U7") (pin "23") (pinfunction "GNDANA_23") (pintype "power_in"))
      (node (ref "U7") (pin "38") (pinfunction "GND_38") (pintype "power_in"))
      (node (ref "U7") (pin "6") (pinfunction "GND_6") (pintype "power_in"))
      (node (ref "U7") (pin "64") (pinfunction "GND_64") (pintype "power_in"))
      (node (ref "U7") (pin "GND") (pinfunction "GND_GND") (pintype "power_in"))
      (node (ref "U8") (pin "2") (pinfunction "A_2") (pintype "bidirectional"))
      (node (ref "U8") (pin "3") (pinfunction "GND_3") (pintype "power_in"))
      (node (ref "U9") (pin "4") (pinfunction "GND_4") (pintype "bidirectional"))
      (node (ref "U9") (pin "8") (pinfunction "~{OE}_8") (pintype "bidirectional"))
      (node (ref "VR1") (pin "5") (pinfunction "GND_5") (pintype "bidirectional"))
      (node (ref "X1") (pin "2") (pinfunction "GND_2") (pintype "bidirectional"))
      (node (ref "X1") (pin "4") (pinfunction "GND_4") (pintype "bidirectional"))
      (node (ref "X2") (pin "2") (pinfunction "GND_2") (pintype "bidirectional"))
      (node (ref "X2") (pin "4") (pinfunction "GND_4") (pintype "bidirectional"))
    )
    (net (code "21") (name "GPS_ENABLE_POWER") (class "Default")
      (node (ref "R23") (pin "1") (pinfunction "1_1") (pintype "passive"))
      (node (ref "SW6") (pin "4") (pinfunction "EN_4") (pintype "bidirectional"))
      (node (ref "U7") (pin "28") (pinfunction "PB07_28") (pintype "bidirectional"))
    )
    (net (code "22") (name "GPS_IN_RX") (class "Default")
      (node (ref "J7") (pin "15") (pinfunction "15_15") (pintype "passive"))
      (node (ref "U5") (pin "5") (pinfunction "RX_5") (pintype "bidirectional"))
      (node (ref "U7") (pin "51") (pinfunction "PA20_51") (pintype "bidirectional"))
    )
    (net (code "23") (name "GPS_OUT_TX") (class "Default")
      (node (ref "J7") (pin "16") (pinfunction "16_16") (pintype "passive"))
      (node (ref "U5") (pin "4") (pinfunction "TX_4") (pintype "bidirectional"))
      (node (ref "U7") (pin "50") (pinfunction "PA19_50") (pintype "bidirectional"))
    )
    (net (code "24") (name "LINUX_ENABLE_POWER") (class "Default")
      (node (ref "Q1") (pin "D1") (pinfunction "D1_D1") (pintype "bidirectional"))
      (node (ref "R25") (pin "1") (pinfunction "1_1") (pintype "passive"))
      (node (ref "SW5") (pin "4") (pinfunction "EN_4") (pintype "bidirectional"))
    )
    (net (code "25") (name "MEMORY_MISO") (class "Default")
      (node (ref "J7") (pin "7") (pinfunction "7_7") (pintype "passive"))
      (node (ref "U1") (pin "2") (pinfunction "SO_2") (pintype "bidirectional"))
      (node (ref "U6") (pin "32") (pinfunction "PA12_32") (pintype "bidirectional"))
      (node (ref "U7") (pin "31") (pinfunction "PA11_31") (pintype "bidirectional"))
    )
    (net (code "26") (name "MEMORY_MOSI") (class "Default")
      (node (ref "J7") (pin "5") (pinfunction "5_5") (pintype "passive"))
      (node (ref "U1") (pin "5") (pinfunction "SI_5") (pintype "bidirectional"))
      (node (ref "U6") (pin "31") (pinfunction "PA11_31") (pintype "bidirectional"))
      (node (ref "U7") (pin "32") (pinfunction "PA12_32") (pintype "bidirectional"))
    )
    (net (code "27") (name "MEMORY_SCLK") (class "Default")
      (node (ref "J7") (pin "6") (pinfunction "6_6") (pintype "passive"))
      (node (ref "U1") (pin "6") (pinfunction "SCK_6") (pintype "bidirectional"))
      (node (ref "U6") (pin "30") (pinfunction "PA10_30") (pintype "bidirectional"))
      (node (ref "U7") (pin "30") (pinfunction "PA10_30") (pintype "bidirectional"))
    )
    (net (code "28") (name "MOD0_IN") (class "Default")
      (node (ref "J4") (pin "9") (pinfunction "MOD0_IN_9") (pintype "bidirectional"))
      (node (ref "U7") (pin "15") (pinfunction "PA04_15") (pintype "bidirectional"))
    )
    (net (code "29") (name "MOD0_OUT") (class "Default")
      (node (ref "J4") (pin "10") (pinfunction "MOD0_OUT_10") (pintype "bidirectional"))
      (node (ref "U7") (pin "40") (pinfunction "PA13_40") (pintype "bidirectional"))
    )
    (net (code "30") (name "MOD1_IN") (class "Default")
      (node (ref "J4") (pin "11") (pinfunction "MOD1_IN_11") (pintype "bidirectional"))
      (node (ref "U7") (pin "16") (pinfunction "PA05_16") (pintype "bidirectional"))
    )
    (net (code "31") (name "MOD1_OUT") (class "Default")
      (node (ref "J4") (pin "12") (pinfunction "MOD1_OUT_12") (pintype "bidirectional"))
      (node (ref "U7") (pin "41") (pinfunction "PA14_41") (pintype "bidirectional"))
    )
    (net (code "32") (name "MOD2_IN") (class "Default")
      (node (ref "J4") (pin "13") (pinfunction "MOD2_IN_13") (pintype "bidirectional"))
      (node (ref "U7") (pin "21") (pinfunction "PA06_21") (pintype "bidirectional"))
    )
    (net (code "33") (name "MOD2_OUT") (class "Default")
      (node (ref "J4") (pin "14") (pinfunction "MOD2_OUT_14") (pintype "bidirectional"))
      (node (ref "U7") (pin "42") (pinfunction "PA15_42") (pintype "bidirectional"))
    )
    (net (code "34") (name "MOD5_IN") (class "Default")
      (node (ref "J4") (pin "15") (pinfunction "MOD5_IN_15") (pintype "bidirectional"))
      (node (ref "U7") (pin "22") (pinfunction "PA07_22") (pintype "bidirectional"))
    )
    (net (code "35") (name "MOD5_OUT") (class "Default")
      (node (ref "J4") (pin "16") (pinfunction "MOD5_OUT_16") (pintype "bidirectional"))
      (node (ref "U7") (pin "43") (pinfunction "PA16_43") (pintype "bidirectional"))
    )
    (net (code "36") (name "MOD6_IN") (class "Default")
      (node (ref "J4") (pin "17") (pinfunction "MOD6_IN_17") (pintype "bidirectional"))
      (node (ref "U7") (pin "26") (pinfunction "PA08_26") (pintype "bidirectional"))
    )
    (net (code "37") (name "MOD6_OUT") (class "Default")
      (node (ref "J4") (pin "18") (pinfunction "MOD6_OUT_18") (pintype "bidirectional"))
      (node (ref "U7") (pin "44") (pinfunction "PA17_44") (pintype "bidirectional"))
    )
    (net (code "38") (name "MOD7_IN") (class "Default")
      (node (ref "J4") (pin "19") (pinfunction "MOD7_IN_19") (pintype "bidirectional"))
      (node (ref "U7") (pin "29") (pinfunction "PA09_29") (pintype "bidirectional"))
    )
    (net (code "39") (name "MOD7_OUT") (class "Default")
      (node (ref "J4") (pin "20") (pinfunction "MOD7_OUT_20") (pintype "bidirectional"))
      (node (ref "U7") (pin "49") (pinfunction "PA18_49") (pintype "bidirectional"))
    )
    (net (code "40") (name "MODSTORAGE_IN") (class "Default")
      (node (ref "J17") (pin "1") (pinfunction "1_1") (pintype "passive"))
      (node (ref "U6") (pin "14") (pinfunction "PB03_14") (pintype "bidirectional"))
      (node (ref "U7") (pin "46") (pinfunction "PB09_46") (pintype "bidirectional"))
    )
    (net (code "41") (name "MODSTORAGE_OUT") (class "Default")
      (node (ref "J17") (pin "2") (pinfunction "2_2") (pintype "passive"))
      (node (ref "U6") (pin "12") (pinfunction "PB01_12") (pintype "bidirectional"))
      (node (ref "U7") (pin "47") (pinfunction "PB10_47") (pintype "bidirectional"))
    )
    (net (code "42") (name "MODULES_SCL") (class "Default")
      (node (ref "J4") (pin "24") (pinfunction "MODULES_SCL_24") (pintype "bidirectional"))
      (node (ref "U10") (pin "14") (pinfunction "B6_14") (pintype "bidirectional"))
      (node (ref "U6") (pin "60") (pinfunction "PA24_60") (pintype "bidirectional"))
      (node (ref "U7") (pin "12") (pinfunction "PB01_12") (pintype "bidirectional"))
      (node (ref "U7") (pin "60") (pinfunction "PA24_60") (pintype "bidirectional"))
    )
    (net (code "43") (name "MODULES_SDA") (class "Default")
      (node (ref "J4") (pin "23") (pinfunction "MODULES_SDA_23") (pintype "bidirectional"))
      (node (ref "U10") (pin "15") (pinfunction "B5_15") (pintype "bidirectional"))
      (node (ref "U6") (pin "59") (pinfunction "PA23_59") (pintype "bidirectional"))
      (node (ref "U7") (pin "14") (pinfunction "PB03_14") (pintype "bidirectional"))
      (node (ref "U7") (pin "59") (pinfunction "PA23_59") (pintype "bidirectional"))
    )
    (net (code "44") (name "Net-(C28-1)") (class "Default")
      (node (ref "C28") (pin "P$1") (pinfunction "1_P$1") (pintype "bidirectional"))
      (node (ref "J10") (pin "2") (pinfunction "2_2") (pintype "passive"))
      (node (ref "VR1") (pin "1") (pinfunction "EN_1") (pintype "bidirectional"))
      (node (ref "VR1") (pin "7") (pinfunction "VIN_7") (pintype "bidirectional"))
    )
    (net (code "45") (name "Net-(D1-PadCATHODE)") (class "Default")
      (node (ref "D1") (pin "CATHODE") (pinfunction "CATHODE_CATHODE") (pintype "bidirectional"))
      (node (ref "J9") (pin "2") (pinfunction "2_2") (pintype "passive"))
    )
    (net (code "46") (name "Net-(D2-B)") (class "Default")
      (node (ref "D2") (pin "3") (pinfunction "B_3") (pintype "output"))
      (node (ref "R6") (pin "1") (pinfunction "1_1") (pintype "passive"))
    )
    (net (code "47") (name "Net-(D2-R)") (class "Default")
      (node (ref "D2") (pin "2") (pinfunction "R_2") (pintype "output"))
      (node (ref "R5") (pin "1") (pinfunction "1_1") (pintype "passive"))
    )
    (net (code "48") (name "Net-(D3-B)") (class "Default")
      (node (ref "D3") (pin "3") (pinfunction "B_3") (pintype "output"))
      (node (ref "R9") (pin "1") (pinfunction "1_1") (pintype "passive"))
    )
    (net (code "49") (name "Net-(D3-G)") (class "Default")
      (node (ref "D3") (pin "4") (pinfunction "G_4") (pintype "output"))
      (node (ref "R8") (pin "1") (pinfunction "1_1") (pintype "passive"))
    )
    (net (code "50") (name "Net-(D3-R)") (class "Default")
      (node (ref "D3") (pin "2") (pinfunction "R_2") (pintype "output"))
      (node (ref "R7") (pin "1") (pinfunction "1_1") (pintype "passive"))
    )
    (net (code "51") (name "Net-(E_1D-GP27_I2C_6_SCL)") (class "Default")
      (node (ref "E_1") (pin "45") (pinfunction "GP27_I2C_6_SCL_45") (pintype "bidirectional"))
      (node (ref "U10") (pin "7") (pinfunction "A6_7") (pintype "bidirectional"))
    )
    (net (code "52") (name "Net-(E_1D-GP28_I2C_6_SDA)") (class "Default")
      (node (ref "E_1") (pin "47") (pinfunction "GP28_I2C_6_SDA_47") (pintype "bidirectional"))
      (node (ref "U10") (pin "6") (pinfunction "A5_6") (pintype "bidirectional"))
    )
    (net (code "53") (name "Net-(E_1G-GP110_SPI_2_FS0)") (class "Default")
      (node (ref "E_1") (pin "53") (pinfunction "GP110_SPI_2_FS0_53") (pintype "bidirectional"))
      (node (ref "J13") (pin "1") (pinfunction "1_1") (pintype "passive"))
    )
    (net (code "54") (name "Net-(E_1G-GP111_SPI_2_FS1)") (class "Default")
      (node (ref "E_1") (pin "51") (pinfunction "GP111_SPI_2_FS1_51") (pintype "bidirectional"))
      (node (ref "J13") (pin "3") (pinfunction "3_3") (pintype "passive"))
    )
    (net (code "55") (name "Net-(E_1J-USB_DN)") (class "Default")
      (node (ref "E_1") (pin "18") (pinfunction "USB_DN_18") (pintype "bidirectional"))
      (node (ref "U9") (pin "5") (pinfunction "D-_5") (pintype "bidirectional"))
    )
    (net (code "56") (name "Net-(E_1J-USB_DP)") (class "Default")
      (node (ref "E_1") (pin "16") (pinfunction "USB_DP_16") (pintype "bidirectional"))
      (node (ref "U9") (pin "3") (pinfunction "D+_3") (pintype "bidirectional"))
    )
    (net (code "57") (name "Net-(E_1J-USB_ID)") (class "Default")
      (node (ref "E_1") (pin "3") (pinfunction "USB_ID_3") (pintype "bidirectional"))
      (node (ref "U8") (pin "4") (pinfunction "Y_4") (pintype "bidirectional"))
    )
    (net (code "58") (name "Net-(FB1-P$1)") (class "Default")
      (node (ref "FB1") (pin "1") (pinfunction "P$1_1") (pintype "bidirectional"))
      (node (ref "U5") (pin "17") (pinfunction "VOUT_17") (pintype "bidirectional"))
    )
    (net (code "59") (name "Net-(FB1-P$2)") (class "Default")
      (node (ref "FB1") (pin "2") (pinfunction "P$2_2") (pintype "bidirectional"))
      (node (ref "J16") (pin "SIG") (pinfunction "ANT_SIG") (pintype "bidirectional"))
      (node (ref "U5") (pin "19") (pinfunction "RFIN_19") (pintype "bidirectional"))
    )
    (net (code "60") (name "Net-(FB3-P$1)") (class "Default")
      (node (ref "C8") (pin "1") (pinfunction "1_1") (pintype "bidirectional"))
      (node (ref "FB3") (pin "1") (pinfunction "P$1_1") (pintype "bidirectional"))
      (node (ref "U6") (pin "24") (pinfunction "ADVREFP_24") (pintype "bidirectional"))
      (node (ref "U6") (pin "25") (pinfunction "VDDANA_25") (pintype "power_in"))
    )
    (net (code "61") (name "Net-(FB4-P$1)") (class "Default")
      (node (ref "C13") (pin "1") (pinfunction "1_1") (pintype "bidirectional"))
      (node (ref "FB4") (pin "1") (pinfunction "P$1_1") (pintype "bidirectional"))
      (node (ref "U7") (pin "24") (pinfunction "ADVREFP_24") (pintype "bidirectional"))
      (node (ref "U7") (pin "25") (pinfunction "VDDANA_25") (pintype "power_in"))
    )
    (net (code "62") (name "Net-(J1-VCC)") (class "Default")
      (node (ref "C27") (pin "1") (pinfunction "1_1") (pintype "bidirectional"))
      (node (ref "J1") (pin "4") (pinfunction "VCC_4") (pintype "bidirectional"))
      (node (ref "J12") (pin "2") (pinfunction "2_2") (pintype "passive"))
      (node (ref "R12") (pin "2") (pinfunction "2_2") (pintype "passive"))
      (node (ref "R13") (pin "2") (pinfunction "2_2") (pintype "passive"))
      (node (ref "R14") (pin "2") (pinfunction "2_2") (pintype "passive"))
      (node (ref "R20") (pin "2") (pinfunction "2_2") (pintype "passive"))
    )
    (net (code "63") (name "Net-(J2-+5V)") (class "Default")
      (node (ref "FB2") (pin "P$2") (pinfunction "P$2_P$2") (pintype "bidirectional"))
      (node (ref "J2") (pin "1") (pinfunction "+5V_1") (pintype "bidirectional"))
    )
    (net (code "64") (name "Net-(J2-D+)") (class "Default")
      (node (ref "C6") (pin "1") (pinfunction "1_1") (pintype "bidirectional"))
      (node (ref "J2") (pin "3") (pinfunction "D+_3") (pintype "bidirectional"))
      (node (ref "R2") (pin "1") (pinfunction "1_1") (pintype "passive"))
    )
    (net (code "65") (name "Net-(J2-D-)") (class "Default")
      (node (ref "C5") (pin "1") (pinfunction "1_1") (pintype "bidirectional"))
      (node (ref "J2") (pin "2") (pinfunction "D-_2") (pintype "bidirectional"))
      (node (ref "R1") (pin "1") (pinfunction "1_1") (pintype "passive"))
    )
    (net (code "66") (name "Net-(J3-D+)") (class "Default")
      (node (ref "J3") (pin "3") (pinfunction "D+_3") (pintype "bidirectional"))
      (node (ref "U9") (pin "1") (pinfunction "D1+_1") (pintype "bidirectional"))
    )
    (net (code "67") (name "Net-(J3-D-)") (class "Default")
      (node (ref "J3") (pin "2") (pinfunction "D-_2") (pintype "bidirectional"))
      (node (ref "U9") (pin "7") (pinfunction "D1-_7") (pintype "bidirectional"))
    )
    (net (code "68") (name "Net-(L1-1)") (class "Default")
      (node (ref "L1") (pin "P$1") (pinfunction "1_P$1") (pintype "bidirectional"))
      (node (ref "VR1") (pin "6") (pinfunction "SW_6") (pintype "bidirectional"))
    )
    (net (code "69") (name "Net-(L2-1)") (class "Default")
      (node (ref "L2") (pin "P$1") (pinfunction "1_P$1") (pintype "bidirectional"))
      (node (ref "U6") (pin "7") (pinfunction "VDDOUT_7") (pintype "power_in"))
    )
    (net (code "70") (name "Net-(L2-2)") (class "Default")
      (node (ref "C12") (pin "1") (pinfunction "1_1") (pintype "bidirectional"))
      (node (ref "C25") (pin "1") (pinfunction "1_1") (pintype "bidirectional"))
      (node (ref "L2") (pin "P$2") (pinfunction "2_P$2") (pintype "bidirectional"))
      (node (ref "U6") (pin "5") (pinfunction "VDDCORE_5") (pintype "power_in"))
    )
    (net (code "71") (name "Net-(L3-1)") (class "Default")
      (node (ref "L3") (pin "P$1") (pinfunction "1_P$1") (pintype "bidirectional"))
      (node (ref "U7") (pin "7") (pinfunction "VDDOUT_7") (pintype "power_in"))
    )
    (net (code "72") (name "Net-(L3-2)") (class "Default")
      (node (ref "C17") (pin "1") (pinfunction "1_1") (pintype "bidirectional"))
      (node (ref "C26") (pin "1") (pinfunction "1_1") (pintype "bidirectional"))
      (node (ref "L3") (pin "P$2") (pinfunction "2_P$2") (pintype "bidirectional"))
      (node (ref "U7") (pin "5") (pinfunction "VDDCORE_5") (pintype "power_in"))
    )
    (net (code "73") (name "Net-(SW5-VLOAD)") (class "Default")
      (node (ref "J10") (pin "1") (pinfunction "1_1") (pintype "passive"))
      (node (ref "SW5") (pin "1") (pinfunction "VLOAD_1") (pintype "bidirectional"))
    )
    (net (code "74") (name "Net-(SW6-VLOAD)") (class "Default")
      (node (ref "J11") (pin "1") (pinfunction "1_1") (pintype "passive"))
      (node (ref "SW6") (pin "1") (pinfunction "VLOAD_1") (pintype "bidirectional"))
    )
    (net (code "75") (name "Net-(SW7-VLOAD)") (class "Default")
      (node (ref "J12") (pin "1") (pinfunction "1_1") (pintype "passive"))
      (node (ref "SW7") (pin "1") (pinfunction "VLOAD_1") (pintype "bidirectional"))
    )
    (net (code "76") (name "Net-(U2-RXD)") (class "Default")
      (node (ref "R4") (pin "1") (pinfunction "1_1") (pintype "passive"))
      (node (ref "U2") (pin "10") (pinfunction "RXD_10") (pintype "bidirectional"))
    )
    (net (code "77") (name "Net-(U2-TXD)") (class "Default")
      (node (ref "R3") (pin "1") (pinfunction "1_1") (pintype "passive"))
      (node (ref "U2") (pin "7") (pinfunction "TXD_7") (pintype "bidirectional"))
    )
    (net (code "78") (name "Net-(U2-USBDM)") (class "Default")
      (node (ref "R1") (pin "2") (pinfunction "2_2") (pintype "passive"))
      (node (ref "U2") (pin "1") (pinfunction "USBDM_1") (pintype "bidirectional"))
    )
    (net (code "79") (name "Net-(U2-USBDP)") (class "Default")
      (node (ref "R2") (pin "2") (pinfunction "2_2") (pintype "passive"))
      (node (ref "U2") (pin "12") (pinfunction "USBDP_12") (pintype "bidirectional"))
    )
    (net (code "80") (name "Net-(U2-VCC)") (class "Default")
      (node (ref "C7") (pin "1") (pinfunction "1_1") (pintype "bidirectional"))
      (node (ref "FB2") (pin "P$1") (pinfunction "P$1_P$1") (pintype "bidirectional"))
      (node (ref "U2") (pin "4") (pinfunction "VCC_4") (pintype "bidirectional"))
    )
    (net (code "81") (name "Net-(U5-VBACKUP)") (class "Default")
      (node (ref "C18") (pin "1") (pinfunction "1_1") (pintype "bidirectional"))
      (node (ref "J11") (pin "2") (pinfunction "2_2") (pintype "passive"))
      (node (ref "U5") (pin "11") (pinfunction "VBACKUP_11") (pintype "bidirectional"))
      (node (ref "U5") (pin "12") (pinfunction "VCC_12") (pintype "bidirectional"))
    )
    (net (code "82") (name "Net-(U6-BIASH)") (class "Default")
      (node (ref "U6") (pin "36") (pinfunction "BIASH_36") (pintype "bidirectional"))
      (node (ref "U6") (pin "37") (pinfunction "BIASL_37") (pintype "bidirectional"))
    )
    (net (code "83") (name "Net-(U6-CAPH)") (class "Default")
      (node (ref "U6") (pin "33") (pinfunction "CAPH_33") (pintype "bidirectional"))
      (node (ref "U6") (pin "34") (pinfunction "CAPL_34") (pintype "bidirectional"))
    )
    (net (code "84") (name "Net-(U6-PA02)") (class "Default")
      (node (ref "R10") (pin "1") (pinfunction "1_1") (pintype "passive"))
      (node (ref "R27") (pin "2") (pinfunction "2_2") (pintype "passive"))
      (node (ref "U6") (pin "3") (pinfunction "PA02_3") (pintype "bidirectional"))
    )
    (net (code "85") (name "Net-(U7-BIASH)") (class "Default")
      (node (ref "U7") (pin "36") (pinfunction "BIASH_36") (pintype "bidirectional"))
      (node (ref "U7") (pin "37") (pinfunction "BIASL_37") (pintype "bidirectional"))
    )
    (net (code "86") (name "Net-(U7-CAPH)") (class "Default")
      (node (ref "U7") (pin "33") (pinfunction "CAPH_33") (pintype "bidirectional"))
      (node (ref "U7") (pin "34") (pinfunction "CAPL_34") (pintype "bidirectional"))
    )
    (net (code "87") (name "Net-(U7-PA02)") (class "Default")
      (node (ref "R11") (pin "1") (pinfunction "1_1") (pintype "passive"))
      (node (ref "R26") (pin "2") (pinfunction "2_2") (pintype "passive"))
      (node (ref "U7") (pin "3") (pinfunction "PA02_3") (pintype "bidirectional"))
    )
    (net (code "88") (name "Net-(U9-S)") (class "Default")
      (node (ref "Q1") (pin "D2") (pinfunction "D2_D2") (pintype "bidirectional"))
      (node (ref "R22") (pin "2") (pinfunction "2_2") (pintype "passive"))
      (node (ref "U9") (pin "10") (pinfunction "S_10") (pintype "bidirectional"))
    )
    (net (code "89") (name "Net-(U10-B7)") (class "Default")
      (node (ref "R6") (pin "2") (pinfunction "2_2") (pintype "passive"))
      (node (ref "U10") (pin "13") (pinfunction "B7_13") (pintype "bidirectional"))
    )
    (net (code "90") (name "PPS") (class "Default")
      (node (ref "J4") (pin "25") (pinfunction "PPS_25") (pintype "bidirectional"))
      (node (ref "U5") (pin "3") (pinfunction "1PPS_3") (pintype "bidirectional"))
      (node (ref "U6") (pin "45") (pinfunction "PB08_45") (pintype "bidirectional"))
      (node (ref "U7") (pin "45") (pinfunction "PB08_45") (pintype "bidirectional"))
    )
    (net (code "91") (name "SD_ENABLE_POWER") (class "Default")
      (node (ref "R24") (pin "1") (pinfunction "1_1") (pintype "passive"))
      (node (ref "SW7") (pin "4") (pinfunction "EN_4") (pintype "bidirectional"))
      (node (ref "U6") (pin "55") (pinfunction "PA21_55") (pintype "bidirectional"))
    )
    (net (code "92") (name "SD_MISO") (class "Default")
      (node (ref "J1") (pin "7") (pinfunction "DATA0/MISO_7") (pintype "bidirectional"))
      (node (ref "J7") (pin "2") (pinfunction "2_2") (pintype "passive"))
      (node (ref "R14") (pin "1") (pinfunction "1_1") (pintype "passive"))
      (node (ref "U6") (pin "42") (pinfunction "PA15_42") (pintype "bidirectional"))
    )
    (net (code "93") (name "SD_MOSI") (class "Default")
      (node (ref "J1") (pin "3") (pinfunction "CMD/MOSI_3") (pintype "bidirectional"))
      (node (ref "J7") (pin "1") (pinfunction "1_1") (pintype "passive"))
      (node (ref "R12") (pin "1") (pinfunction "1_1") (pintype "passive"))
      (node (ref "U6") (pin "43") (pinfunction "PA16_43") (pintype "bidirectional"))
    )
    (net (code "94") (name "SD_SCLK") (class "Default")
      (node (ref "J1") (pin "5") (pinfunction "CLK_5") (pintype "bidirectional"))
      (node (ref "J7") (pin "3") (pinfunction "3_3") (pintype "passive"))
      (node (ref "U6") (pin "41") (pinfunction "PA14_41") (pintype "bidirectional"))
    )
    (net (code "95") (name "SMBCLK") (class "Default")
      (node (ref "J4") (pin "5") (pinfunction "SMBCLK_5") (pintype "bidirectional"))
      (node (ref "U7") (pin "56") (pinfunction "PA22_56") (pintype "bidirectional"))
    )
    (net (code "96") (name "SMBDATA") (class "Default")
      (node (ref "J4") (pin "3") (pinfunction "SMBDATA_3") (pintype "bidirectional"))
      (node (ref "U7") (pin "55") (pinfunction "PA21_55") (pintype "bidirectional"))
    )
    (net (code "97") (name "STORAGE_DEBUG_GPIO1") (class "Default")
      (node (ref "J4") (pin "201") (pinfunction "DBG_GPIO1_201") (pintype "bidirectional"))
      (node (ref "U6") (pin "19") (pinfunction "PB04_19") (pintype "bidirectional"))
    )
    (net (code "98") (name "STORAGE_DEBUG_GPIO2") (class "Default")
      (node (ref "J4") (pin "204") (pinfunction "DBG_GPIO2_204") (pintype "bidirectional"))
      (node (ref "U6") (pin "20") (pinfunction "PB05_20") (pintype "bidirectional"))
    )
    (net (code "99") (name "STORAGE_DEBUG_RX") (class "Default")
      (node (ref "J4") (pin "203") (pinfunction "DBG_RX_203") (pintype "bidirectional"))
      (node (ref "U6") (pin "46") (pinfunction "PB09_46") (pintype "bidirectional"))
    )
    (net (code "100") (name "STORAGE_DEBUG_TX") (class "Default")
      (node (ref "J4") (pin "202") (pinfunction "DBG_TX_202") (pintype "bidirectional"))
      (node (ref "U6") (pin "47") (pinfunction "PB10_47") (pintype "bidirectional"))
    )
    (net (code "101") (name "STORAGE_INTERRUPT") (class "Default")
      (node (ref "U6") (pin "26") (pinfunction "PA08_26") (pintype "bidirectional"))
      (node (ref "U7") (pin "53") (pinfunction "PB12_53") (pintype "bidirectional"))
    )
    (net (code "102") (name "STORAGE_SWDCLK") (class "Default")
      (node (ref "J14") (pin "4") (pinfunction "SWDCLK_4") (pintype "bidirectional"))
      (node (ref "J4") (pin "206") (pinfunction "DBG_SWDCLK_206") (pintype "bidirectional"))
      (node (ref "R17") (pin "1") (pinfunction "1_1") (pintype "passive"))
      (node (ref "U6") (pin "9") (pinfunction "TCK_9") (pintype "bidirectional"))
    )
    (net (code "103") (name "STORAGE_SWDIO") (class "Default")
      (node (ref "J14") (pin "2") (pinfunction "SWDIO_2") (pintype "bidirectional"))
      (node (ref "J4") (pin "207") (pinfunction "DBG_SWDIO_207") (pintype "bidirectional"))
      (node (ref "R16") (pin "1") (pinfunction "1_1") (pintype "passive"))
      (node (ref "U6") (pin "10") (pinfunction "PA03_10") (pintype "bidirectional"))
    )
    (net (code "104") (name "STORAGE_XIN") (class "Default")
      (node (ref "C1") (pin "1") (pinfunction "1_1") (pintype "bidirectional"))
      (node (ref "U6") (pin "1") (pinfunction "PA00_1") (pintype "bidirectional"))
      (node (ref "X1") (pin "3") (pinfunction "2_3") (pintype "bidirectional"))
    )
    (net (code "105") (name "STORAGE_XOUT") (class "Default")
      (node (ref "C2") (pin "1") (pinfunction "1_1") (pintype "bidirectional"))
      (node (ref "U6") (pin "2") (pinfunction "PA01_2") (pintype "bidirectional"))
      (node (ref "X1") (pin "1") (pinfunction "1_1") (pintype "bidirectional"))
    )
    (net (code "106") (name "USB_MOD_D+") (class "Default")
      (node (ref "J4") (pin "27") (pinfunction "USB_D+_27") (pintype "bidirectional"))
      (node (ref "U9") (pin "2") (pinfunction "D2+_2") (pintype "bidirectional"))
    )
    (net (code "107") (name "USB_MOD_D-") (class "Default")
      (node (ref "J4") (pin "28") (pinfunction "USB_D-_28") (pintype "bidirectional"))
      (node (ref "U9") (pin "6") (pinfunction "D2-_6") (pintype "bidirectional"))
    )
    (net (code "108") (name "USB_VBUS") (class "Default")
      (node (ref "D1") (pin "ANODE") (pinfunction "ANODE_ANODE") (pintype "bidirectional"))
      (node (ref "E_1") (pin "20") (pinfunction "USB_VBUS_20") (pintype "bidirectional"))
      (node (ref "J3") (pin "1") (pinfunction "+5V_1") (pintype "bidirectional"))
      (node (ref "Q1") (pin "G2") (pinfunction "G2_G2") (pintype "input"))
      (node (ref "R21") (pin "1") (pinfunction "1_1") (pintype "passive"))
      (node (ref "U8") (pin "1") (pinfunction "~{OE}_1") (pintype "bidirectional"))
    )
    (net (code "109") (name "VCC_CONTROLLER") (class "Default")
      (node (ref "C10") (pin "1") (pinfunction "1_1") (pintype "bidirectional"))
      (node (ref "C11") (pin "1") (pinfunction "1_1") (pintype "bidirectional"))
      (node (ref "C14") (pin "1") (pinfunction "1_1") (pintype "bidirectional"))
      (node (ref "C15") (pin "1") (pinfunction "1_1") (pintype "bidirectional"))
      (node (ref "C16") (pin "1") (pinfunction "1_1") (pintype "bidirectional"))
      (node (ref "C19") (pin "1") (pinfunction "1_1") (pintype "bidirectional"))
      (node (ref "C21") (pin "2") (pinfunction "2_2") (pintype "bidirectional"))
      (node (ref "C29") (pin "1") (pinfunction "1_1") (pintype "bidirectional"))
      (node (ref "C9") (pin "1") (pinfunction "1_1") (pintype "bidirectional"))
      (node (ref "D3") (pin "1") (pinfunction "VDD_1") (pintype "bidirectional"))
      (node (ref "FB3") (pin "2") (pinfunction "P$2_2") (pintype "bidirectional"))
      (node (ref "FB4") (pin "2") (pinfunction "P$2_2") (pintype "bidirectional"))
      (node (ref "J14") (pin "1") (pinfunction "VCC_1") (pintype "bidirectional"))
      (node (ref "J15") (pin "1") (pinfunction "VCC_1") (pintype "bidirectional"))
      (node (ref "J4") (pin "2") (pinfunction "VCC_CONTROLLER_2") (pintype "bidirectional"))
      (node (ref "J7") (pin "20") (pinfunction "20_20") (pintype "passive"))
      (node (ref "R10") (pin "2") (pinfunction "2_2") (pintype "passive"))
      (node (ref "R11") (pin "2") (pinfunction "2_2") (pintype "passive"))
      (node (ref "R16") (pin "2") (pinfunction "2_2") (pintype "passive"))
      (node (ref "R17") (pin "2") (pinfunction "2_2") (pintype "passive"))
      (node (ref "R18") (pin "2") (pinfunction "2_2") (pintype "passive"))
      (node (ref "R19") (pin "2") (pinfunction "2_2") (pintype "passive"))
      (node (ref "R23") (pin "2") (pinfunction "2_2") (pintype "passive"))
      (node (ref "R24") (pin "2") (pinfunction "2_2") (pintype "passive"))
      (node (ref "SW6") (pin "3") (pinfunction "VSUPP_3") (pintype "bidirectional"))
      (node (ref "SW7") (pin "3") (pinfunction "VSUPP_3") (pintype "bidirectional"))
      (node (ref "U1") (pin "3") (pinfunction "~{WP}_3") (pintype "bidirectional"))
      (node (ref "U1") (pin "7") (pinfunction "~{HOLD}_7") (pintype "bidirectional"))
      (node (ref "U1") (pin "8") (pinfunction "VDD_8") (pintype "bidirectional"))
      (node (ref "U10") (pin "19") (pinfunction "VCCB_19") (pintype "bidirectional"))
      (node (ref "U3") (pin "2") (pinfunction "VCC_2") (pintype "bidirectional"))
      (node (ref "U4") (pin "2") (pinfunction "VCC_2") (pintype "bidirectional"))
      (node (ref "U6") (pin "35") (pinfunction "VLCD_35") (pintype "bidirectional"))
      (node (ref "U6") (pin "39") (pinfunction "VLCDIN_39") (pintype "power_in"))
      (node (ref "U6") (pin "52") (pinfunction "VDDIO_52") (pintype "power_in"))
      (node (ref "U6") (pin "61") (pinfunction "VDDIO_61") (pintype "power_in"))
      (node (ref "U6") (pin "8") (pinfunction "VDDIN_8") (pintype "power_in"))
      (node (ref "U7") (pin "35") (pinfunction "VLCD_35") (pintype "bidirectional"))
      (node (ref "U7") (pin "39") (pinfunction "VLCDIN_39") (pintype "power_in"))
      (node (ref "U7") (pin "52") (pinfunction "VDDIO_52") (pintype "power_in"))
      (node (ref "U7") (pin "61") (pinfunction "VDDIO_61") (pintype "power_in"))
      (node (ref "U7") (pin "8") (pinfunction "VDDIN_8") (pintype "power_in"))
    )
    (net (code "110") (name "VCC_LINUX") (class "Default")
      (node (ref "J4") (pin "4") (pinfunction "VCC_LINUX_4") (pintype "bidirectional"))
      (node (ref "J7") (pin "17") (pinfunction "17_17") (pintype "passive"))
      (node (ref "J9") (pin "1") (pinfunction "1_1") (pintype "passive"))
      (node (ref "R25") (pin "2") (pinfunction "2_2") (pintype "passive"))
      (node (ref "SW5") (pin "3") (pinfunction "VSUPP_3") (pintype "bidirectional"))
      (node (ref "U8") (pin "5") (pinfunction "VCC_5") (pintype "power_in"))
    )
    (net (code "111") (name "VCC_LINUX_1V8") (class "Default")
      (node (ref "C23") (pin "1") (pinfunction "1_1") (pintype "bidirectional"))
      (node (ref "C24") (pin "2") (pinfunction "2_2") (pintype "bidirectional"))
      (node (ref "E_1") (pin "12") (pinfunction "1.8V_12") (pintype "bidirectional"))
      (node (ref "J7") (pin "14") (pinfunction "14_14") (pintype "passive"))
      (node (ref "R28") (pin "1") (pinfunction "1_1") (pintype "passive"))
      (node (ref "U10") (pin "10") (pinfunction "OE_10") (pintype "bidirectional"))
      (node (ref "U10") (pin "2") (pinfunction "VCCA_2") (pintype "bidirectional"))
      (node (ref "U2") (pin "9") (pinfunction "VCCIO_9") (pintype "bidirectional"))
    )
    (net (code "112") (name "VCC_LINUX_3V3") (class "Default")
      (node (ref "C20") (pin "1") (pinfunction "1_1") (pintype "bidirectional"))
      (node (ref "C22") (pin "1") (pinfunction "1_1") (pintype "bidirectional"))
      (node (ref "C30") (pin "P$1") (pinfunction "1_P$1") (pintype "bidirectional"))
      (node (ref "D2") (pin "1") (pinfunction "VDD_1") (pintype "bidirectional"))
      (node (ref "E_1") (pin "14") (pinfunction "DCIN_14") (pintype "bidirectional"))
      (node (ref "E_1") (pin "2") (pinfunction "VSYS_2") (pintype "bidirectional"))
      (node (ref "E_1") (pin "4") (pinfunction "VSYS_4") (pintype "bidirectional"))
      (node (ref "E_1") (pin "6") (pinfunction "VSYS_6") (pintype "bidirectional"))
      (node (ref "J7") (pin "18") (pinfunction "18_18") (pintype "passive"))
      (node (ref "L1") (pin "P$2") (pinfunction "2_P$2") (pintype "bidirectional"))
      (node (ref "R15") (pin "2") (pinfunction "2_2") (pintype "passive"))
      (node (ref "R22") (pin "1") (pinfunction "1_1") (pintype "passive"))
      (node (ref "U9") (pin "9") (pinfunction "VCC_9") (pintype "bidirectional"))
      (node (ref "VR1") (pin "3") (pinfunction "FB_3") (pintype "bidirectional"))
      (node (ref "VR1") (pin "4") (pinfunction "VOS_4") (pintype "bidirectional"))
    )
    (net (code "113") (name "unconnected-(D2-G-Pad4)") (class "Default")
      (node (ref "D2") (pin "4") (pinfunction "G_4") (pintype "output"))
    )
    (net (code "114") (name "unconnected-(E_1A-3.3V-Pad8)") (class "Default")
      (node (ref "E_1") (pin "8") (pinfunction "3.3V_8") (pintype "bidirectional"))
    )
    (net (code "115") (name "unconnected-(E_1A-3.3V-Pad10)") (class "Default")
      (node (ref "E_1") (pin "10") (pinfunction "3.3V_10") (pintype "bidirectional"))
    )
    (net (code "116") (name "unconnected-(E_1A-FW_RCVR-Pad69)") (class "Default")
      (node (ref "E_1") (pin "69") (pinfunction "FW_RCVR_69") (pintype "bidirectional"))
    )
    (net (code "117") (name "unconnected-(E_1A-MSIC_SLP_CLK-Pad7)") (class "Default")
      (node (ref "E_1") (pin "7") (pinfunction "MSIC_SLP_CLK_7") (pintype "bidirectional"))
    )
    (net (code "118") (name "unconnected-(E_1A-OSC_CLK_OUT_0-Pad67)") (class "Default")
      (node (ref "E_1") (pin "67") (pinfunction "OSC_CLK_OUT_0_67") (pintype "bidirectional"))
    )
    (net (code "119") (name "unconnected-(E_1A-RCVR_MODE-Pad31)") (class "Default")
      (node (ref "E_1") (pin "31") (pinfunction "RCVR_MODE_31") (pintype "bidirectional"))
    )
    (net (code "120") (name "unconnected-(E_1A-RESET_OUT#-Pad36)") (class "Default")
      (node (ref "E_1") (pin "36") (pinfunction "RESET_OUT#_36") (pintype "bidirectional"))
    )
    (net (code "121") (name "unconnected-(E_1A-V_VAT_BKUP-Pad23)") (class "Default")
      (node (ref "E_1") (pin "23") (pinfunction "V_VAT_BKUP_23") (pintype "bidirectional"))
    )
    (net (code "122") (name "unconnected-(E_1B-GP13_PWM1-Pad33)") (class "Default")
      (node (ref "E_1") (pin "33") (pinfunction "GP13_PWM1_33") (pintype "bidirectional"))
    )
    (net (code "123") (name "unconnected-(E_1B-GP14-Pad48)") (class "Default")
      (node (ref "E_1") (pin "48") (pinfunction "GP14_48") (pintype "bidirectional"))
    )
    (net (code "124") (name "unconnected-(E_1B-GP15-Pad42)") (class "Default")
      (node (ref "E_1") (pin "42") (pinfunction "GP15_42") (pintype "bidirectional"))
    )
    (net (code "125") (name "unconnected-(E_1B-GP44-Pad24)") (class "Default")
      (node (ref "E_1") (pin "24") (pinfunction "GP44_24") (pintype "bidirectional"))
    )
    (net (code "126") (name "unconnected-(E_1B-GP45-Pad26)") (class "Default")
      (node (ref "E_1") (pin "26") (pinfunction "GP45_26") (pintype "bidirectional"))
    )
    (net (code "127") (name "unconnected-(E_1B-GP46-Pad28)") (class "Default")
      (node (ref "E_1") (pin "28") (pinfunction "GP46_28") (pintype "bidirectional"))
    )
    (net (code "128") (name "unconnected-(E_1B-GP47-Pad30)") (class "Default")
      (node (ref "E_1") (pin "30") (pinfunction "GP47_30") (pintype "bidirectional"))
    )
    (net (code "129") (name "unconnected-(E_1B-GP48-Pad32)") (class "Default")
      (node (ref "E_1") (pin "32") (pinfunction "GP48_32") (pintype "bidirectional"))
    )
    (net (code "130") (name "unconnected-(E_1B-GP49-Pad34)") (class "Default")
      (node (ref "E_1") (pin "34") (pinfunction "GP49_34") (pintype "bidirectional"))
    )
    (net (code "131") (name "unconnected-(E_1B-GP165-Pad25)") (class "Default")
      (node (ref "E_1") (pin "25") (pinfunction "GP165_25") (pintype "bidirectional"))
    )
    (net (code "132") (name "unconnected-(E_1B-GP183_PWM3-Pad39)") (class "Default")
      (node (ref "E_1") (pin "39") (pinfunction "GP183_PWM3_39") (pintype "bidirectional"))
    )
    (net (code "133") (name "unconnected-(E_1C-GP19_I2C_1_SCL-Pad41)") (class "Default")
      (node (ref "E_1") (pin "41") (pinfunction "GP19_I2C_1_SCL_41") (pintype "bidirectional"))
    )
    (net (code "134") (name "unconnected-(E_1C-GP20_I2C_1_SDA-Pad43)") (class "Default")
      (node (ref "E_1") (pin "43") (pinfunction "GP20_I2C_1_SDA_43") (pintype "bidirectional"))
    )
    (net (code "135") (name "unconnected-(E_1E-GP40_I2S_2_CLK-Pad52)") (class "Default")
      (node (ref "E_1") (pin "52") (pinfunction "GP40_I2S_2_CLK_52") (pintype "bidirectional"))
    )
    (net (code "136") (name "unconnected-(E_1E-GP41_I2S_2_FS-Pad54)") (class "Default")
      (node (ref "E_1") (pin "54") (pinfunction "GP41_I2S_2_FS_54") (pintype "bidirectional"))
    )
    (net (code "137") (name "unconnected-(E_1E-GP42_I2S_2_RXD-Pad50)") (class "Default")
      (node (ref "E_1") (pin "50") (pinfunction "GP42_I2S_2_RXD_50") (pintype "bidirectional"))
    )
    (net (code "138") (name "unconnected-(E_1E-GP43_I2S_2_TXD-Pad56)") (class "Default")
      (node (ref "E_1") (pin "56") (pinfunction "GP43_I2S_2_TXD_56") (pintype "bidirectional"))
    )
    (net (code "139") (name "unconnected-(E_1F-GP77_SD_0_CD#-Pad60)") (class "Default")
      (node (ref "E_1") (pin "60") (pinfunction "GP77_SD_0_CD#_60") (pintype "bidirectional"))
    )
    (net (code "140") (name "unconnected-(E_1F-GP78_SD_0_CLK-Pad58)") (class "Default")
      (node (ref "E_1") (pin "58") (pinfunction "GP78_SD_0_CLK_58") (pintype "bidirectional"))
    )
    (net (code "141") (name "unconnected-(E_1F-GP79_SD_0_CMD-Pad62)") (class "Default")
      (node (ref "E_1") (pin "62") (pinfunction "GP79_SD_0_CMD_62") (pintype "bidirectional"))
    )
    (net (code "142") (name "unconnected-(E_1F-GP80_SD_0_DAT0-Pad66)") (class "Default")
      (node (ref "E_1") (pin "66") (pinfunction "GP80_SD_0_DAT0_66") (pintype "bidirectional"))
    )
    (net (code "143") (name "unconnected-(E_1F-GP81_SD_0_DAT1-Pad70)") (class "Default")
      (node (ref "E_1") (pin "70") (pinfunction "GP81_SD_0_DAT1_70") (pintype "bidirectional"))
    )
    (net (code "144") (name "unconnected-(E_1F-GP82_SD_0_DAT2-Pad64)") (class "Default")
      (node (ref "E_1") (pin "64") (pinfunction "GP82_SD_0_DAT2_64") (pintype "bidirectional"))
    )
    (net (code "145") (name "unconnected-(E_1F-GP83_SD_0_DAT3-Pad68)") (class "Default")
      (node (ref "E_1") (pin "68") (pinfunction "GP83_SD_0_DAT3_68") (pintype "bidirectional"))
    )
    (net (code "146") (name "unconnected-(E_1F-GP84_SD_0_CLK_FB-Pad44)") (class "Default")
      (node (ref "E_1") (pin "44") (pinfunction "GP84_SD_0_CLK_FB_44") (pintype "bidirectional"))
    )
    (net (code "147") (name "unconnected-(E_1H-GP128_UART_1_CTS-Pad65)") (class "Default")
      (node (ref "E_1") (pin "65") (pinfunction "GP128_UART_1_CTS_65") (pintype "bidirectional"))
    )
    (net (code "148") (name "unconnected-(E_1H-GP129_UART_1_RTS-Pad63)") (class "Default")
      (node (ref "E_1") (pin "63") (pinfunction "GP129_UART_1_RTS_63") (pintype "bidirectional"))
    )
    (net (code "149") (name "unconnected-(E_1H-GP130_UART_1_RX-Pad61)") (class "Default")
      (node (ref "E_1") (pin "61") (pinfunction "GP130_UART_1_RX_61") (pintype "bidirectional"))
    )
    (net (code "150") (name "unconnected-(E_1H-GP131_UART_1_TX-Pad46)") (class "Default")
      (node (ref "E_1") (pin "46") (pinfunction "GP131_UART_1_TX_46") (pintype "bidirectional"))
    )
    (net (code "151") (name "unconnected-(E_1J-FAULT-Pad19)") (class "Default")
      (node (ref "E_1") (pin "19") (pinfunction "FAULT_19") (pintype "bidirectional"))
    )
    (net (code "152") (name "unconnected-(E_1J-PSW-Pad21)") (class "Default")
      (node (ref "E_1") (pin "21") (pinfunction "PSW_21") (pintype "bidirectional"))
    )
    (net (code "153") (name "unconnected-(J1-DATA1{slash}RSV-Pad8)") (class "Default")
      (node (ref "J1") (pin "8") (pinfunction "DATA1/RSV_8") (pintype "bidirectional"))
    )
    (net (code "154") (name "unconnected-(J1-DATA2{slash}NC-Pad1)") (class "Default")
      (node (ref "J1") (pin "1") (pinfunction "DATA2/NC_1") (pintype "bidirectional"))
    )
    (net (code "155") (name "unconnected-(J2-ID-Pad4)") (class "Default")
      (node (ref "J2") (pin "4") (pinfunction "ID_4") (pintype "bidirectional"))
    )
    (net (code "156") (name "unconnected-(J3-ID-Pad4)") (class "Default")
      (node (ref "J3") (pin "4") (pinfunction "ID_4") (pintype "bidirectional"))
    )
    (net (code "157") (name "unconnected-(J14-SWO-Pad6)") (class "Default")
      (node (ref "J14") (pin "6") (pinfunction "SWO_6") (pintype "bidirectional"))
    )
    (net (code "158") (name "unconnected-(J15-SWO-Pad6)") (class "Default")
      (node (ref "J15") (pin "6") (pinfunction "SWO_6") (pintype "bidirectional"))
    )
    (net (code "159") (name "unconnected-(U2-3V3OUT-Pad3)") (class "Default")
      (node (ref "U2") (pin "3") (pinfunction "3V3OUT_3") (pintype "bidirectional"))
    )
    (net (code "160") (name "unconnected-(U2-CBUS0-Pad6)") (class "Default")
      (node (ref "U2") (pin "6") (pinfunction "CBUS0_6") (pintype "bidirectional"))
    )
    (net (code "161") (name "unconnected-(U2-~{CTS}-Pad11)") (class "Default")
      (node (ref "U2") (pin "11") (pinfunction "~{CTS}_11") (pintype "bidirectional"))
    )
    (net (code "162") (name "unconnected-(U2-~{RESET}-Pad2)") (class "Default")
      (node (ref "U2") (pin "2") (pinfunction "~{RESET}_2") (pintype "bidirectional"))
    )
    (net (code "163") (name "unconnected-(U2-~{RTS}-Pad8)") (class "Default")
      (node (ref "U2") (pin "8") (pinfunction "~{RTS}_8") (pintype "bidirectional"))
    )
    (net (code "164") (name "unconnected-(U5-~{RESET}-Pad8)") (class "Default")
      (node (ref "U5") (pin "8") (pinfunction "~{RESET}_8") (pintype "bidirectional"))
    )
    (net (code "165") (name "unconnected-(U6-PA04-Pad15)") (class "Default")
      (node (ref "U6") (pin "15") (pinfunction "PA04_15") (pintype "bidirectional"))
    )
    (net (code "166") (name "unconnected-(U6-PA25-Pad62)") (class "Default")
      (node (ref "U6") (pin "62") (pinfunction "PA25_62") (pintype "bidirectional"))
    )
    (net (code "167") (name "unconnected-(U6-PA26-Pad63)") (class "Default")
      (node (ref "U6") (pin "63") (pinfunction "PA26_63") (pintype "bidirectional"))
    )
    (net (code "168") (name "unconnected-(U6-PB00-Pad11)") (class "Default")
      (node (ref "U6") (pin "11") (pinfunction "PB00_11") (pintype "bidirectional"))
    )
    (net (code "169") (name "unconnected-(U6-PB02-Pad13)") (class "Default")
      (node (ref "U6") (pin "13") (pinfunction "PB02_13") (pintype "bidirectional"))
    )
    (net (code "170") (name "unconnected-(U6-PB06-Pad27)") (class "Default")
      (node (ref "U6") (pin "27") (pinfunction "PB06_27") (pintype "bidirectional"))
    )
    (net (code "171") (name "unconnected-(U6-PB07-Pad28)") (class "Default")
      (node (ref "U6") (pin "28") (pinfunction "PB07_28") (pintype "bidirectional"))
    )
    (net (code "172") (name "unconnected-(U6-PB11-Pad48)") (class "Default")
      (node (ref "U6") (pin "48") (pinfunction "PB11_48") (pintype "bidirectional"))
    )
    (net (code "173") (name "unconnected-(U6-PB12-Pad53)") (class "Default")
      (node (ref "U6") (pin "53") (pinfunction "PB12_53") (pintype "bidirectional"))
    )
    (net (code "174") (name "unconnected-(U6-PB13-Pad54)") (class "Default")
      (node (ref "U6") (pin "54") (pinfunction "PB13_54") (pintype "bidirectional"))
    )
    (net (code "175") (name "unconnected-(U6-XIN32-Pad17)") (class "Default")
      (node (ref "U6") (pin "17") (pinfunction "XIN32_17") (pintype "bidirectional"))
    )
    (net (code "176") (name "unconnected-(U6-XOUT32-Pad18)") (class "Default")
      (node (ref "U6") (pin "18") (pinfunction "XOUT32_18") (pintype "bidirectional"))
    )
    (net (code "177") (name "unconnected-(U7-PB00-Pad11)") (class "Default")
      (node (ref "U7") (pin "11") (pinfunction "PB00_11") (pintype "bidirectional"))
    )
    (net (code "178") (name "unconnected-(U7-PB02-Pad13)") (class "Default")
      (node (ref "U7") (pin "13") (pinfunction "PB02_13") (pintype "bidirectional"))
    )
    (net (code "179") (name "unconnected-(U7-XIN32-Pad17)") (class "Default")
      (node (ref "U7") (pin "17") (pinfunction "XIN32_17") (pintype "bidirectional"))
    )
    (net (code "180") (name "unconnected-(U7-XOUT32-Pad18)") (class "Default")
      (node (ref "U7") (pin "18") (pinfunction "XOUT32_18") (pintype "bidirectional"))
    )
    (net (code "181") (name "unconnected-(VR1-PG-Pad2)") (class "Default")
      (node (ref "VR1") (pin "2") (pinfunction "PG_2") (pintype "bidirectional"))
    )
    (net (code "182") (name "~{BACKPLANE_RESET}") (class "Default")
      (node (ref "J4") (pin "22") (pinfunction "~{BACKPLANE_RESET}_22") (pintype "bidirectional"))
      (node (ref "SW2") (pin "1") (pinfunction "P$1_1") (pintype "passive"))
      (node (ref "U6") (pin "58") (pinfunction "PB15_58") (pintype "bidirectional"))
    )
    (net (code "183") (name "~{CONTROLLER_LED}") (class "Default")
      (node (ref "R9") (pin "2") (pinfunction "2_2") (pintype "passive"))
      (node (ref "U7") (pin "48") (pinfunction "PB11_48") (pintype "bidirectional"))
    )
    (net (code "184") (name "~{CONTROLLER_RESET}") (class "Default")
      (node (ref "J15") (pin "3") (pinfunction "~{RESET}_3") (pintype "bidirectional"))
      (node (ref "J4") (pin "105") (pinfunction "DBG_~{RESET}_105") (pintype "bidirectional"))
      (node (ref "SW3") (pin "1") (pinfunction "P$1_1") (pintype "passive"))
      (node (ref "U3") (pin "1") (pinfunction "~{RST}_1") (pintype "bidirectional"))
      (node (ref "U7") (pin "4") (pinfunction "~{RESET}_4") (pintype "bidirectional"))
    )
    (net (code "185") (name "~{EDISON_PWRBTN}") (class "Default")
      (node (ref "E_1") (pin "17") (pinfunction "PWRBTN#_17") (pintype "bidirectional"))
      (node (ref "J8") (pin "2") (pinfunction "2_2") (pintype "passive"))
      (node (ref "R15") (pin "1") (pinfunction "1_1") (pintype "passive"))
      (node (ref "SW1") (pin "1") (pinfunction "P$1_1") (pintype "passive"))
      (node (ref "U6") (pin "16") (pinfunction "PA05_16") (pintype "bidirectional"))
    )
    (net (code "186") (name "~{EDISON_SPI_CS_1V8}") (class "Default")
      (node (ref "J13") (pin "2") (pinfunction "2_2") (pintype "passive"))
      (node (ref "J7") (pin "13") (pinfunction "13_13") (pintype "passive"))
      (node (ref "U10") (pin "5") (pinfunction "A4_5") (pintype "bidirectional"))
    )
    (net (code "187") (name "~{EDISON_SPI_CS}") (class "Default")
      (node (ref "U10") (pin "16") (pinfunction "B4_16") (pintype "bidirectional"))
      (node (ref "U6") (pin "56") (pinfunction "PA22_56") (pintype "bidirectional"))
    )
    (net (code "188") (name "~{ENABLE_LINUX}") (class "Default")
      (node (ref "Q1") (pin "G1") (pinfunction "G1_G1") (pintype "input"))
      (node (ref "U6") (pin "21") (pinfunction "PA06_21") (pintype "bidirectional"))
    )
    (net (code "189") (name "~{FRAM_CS}") (class "Default")
      (node (ref "J7") (pin "9") (pinfunction "9_9") (pintype "passive"))
      (node (ref "U1") (pin "1") (pinfunction "~{CS}_1") (pintype "bidirectional"))
      (node (ref "U7") (pin "62") (pinfunction "PA25_62") (pintype "bidirectional"))
    )
    (net (code "190") (name "~{SD_CS}") (class "Default")
      (node (ref "J1") (pin "2") (pinfunction "DATA3-CD/CS_N_2") (pintype "bidirectional"))
      (node (ref "J7") (pin "4") (pinfunction "4_4") (pintype "passive"))
      (node (ref "R13") (pin "1") (pinfunction "1_1") (pintype "passive"))
      (node (ref "U6") (pin "40") (pinfunction "PA13_40") (pintype "bidirectional"))
    )
    (net (code "191") (name "~{SD_DETECT}") (class "Default")
      (node (ref "J1") (pin "A") (pinfunction "A_A") (pintype "bidirectional"))
      (node (ref "R20") (pin "1") (pinfunction "1_1") (pintype "passive"))
      (node (ref "U6") (pin "44") (pinfunction "PA17_44") (pintype "bidirectional"))
    )
    (net (code "192") (name "~{SMBALERT}") (class "Default")
      (node (ref "J4") (pin "6") (pinfunction "~{SMBALERT}_6") (pintype "bidirectional"))
      (node (ref "U7") (pin "63") (pinfunction "PA26_63") (pintype "bidirectional"))
    )
    (net (code "193") (name "~{STORAGE_CS}") (class "Default")
      (node (ref "J7") (pin "8") (pinfunction "8_8") (pintype "passive"))
      (node (ref "U6") (pin "29") (pinfunction "PA09_29") (pintype "bidirectional"))
      (node (ref "U7") (pin "54") (pinfunction "PB13_54") (pintype "bidirectional"))
    )
    (net (code "194") (name "~{STORAGE_LED}") (class "Default")
      (node (ref "R8") (pin "2") (pinfunction "2_2") (pintype "passive"))
      (node (ref "U6") (pin "22") (pinfunction "PA07_22") (pintype "bidirectional"))
    )
    (net (code "195") (name "~{STORAGE_RESET}") (class "Default")
      (node (ref "J14") (pin "3") (pinfunction "~{RESET}_3") (pintype "bidirectional"))
      (node (ref "J4") (pin "205") (pinfunction "DBG_~{RESET}_205") (pintype "bidirectional"))
      (node (ref "SW4") (pin "1") (pinfunction "P$1_1") (pintype "passive"))
      (node (ref "U4") (pin "1") (pinfunction "~{RST}_1") (pintype "bidirectional"))
      (node (ref "U6") (pin "4") (pinfunction "~{RESET}_4") (pintype "bidirectional"))
    )
    (net (code "196") (name "~{WATCHDOG}") (class "Default")
      (node (ref "J4") (pin "7") (pinfunction "~{WATCHDOG}_7") (pintype "bidirectional"))
      (node (ref "U7") (pin "27") (pinfunction "PB06_27") (pintype "bidirectional"))
    )
  )
)
